# EFP01_-_Front_Panel_Board.net
KiCad netlist of a schematic drawn in EAGLE
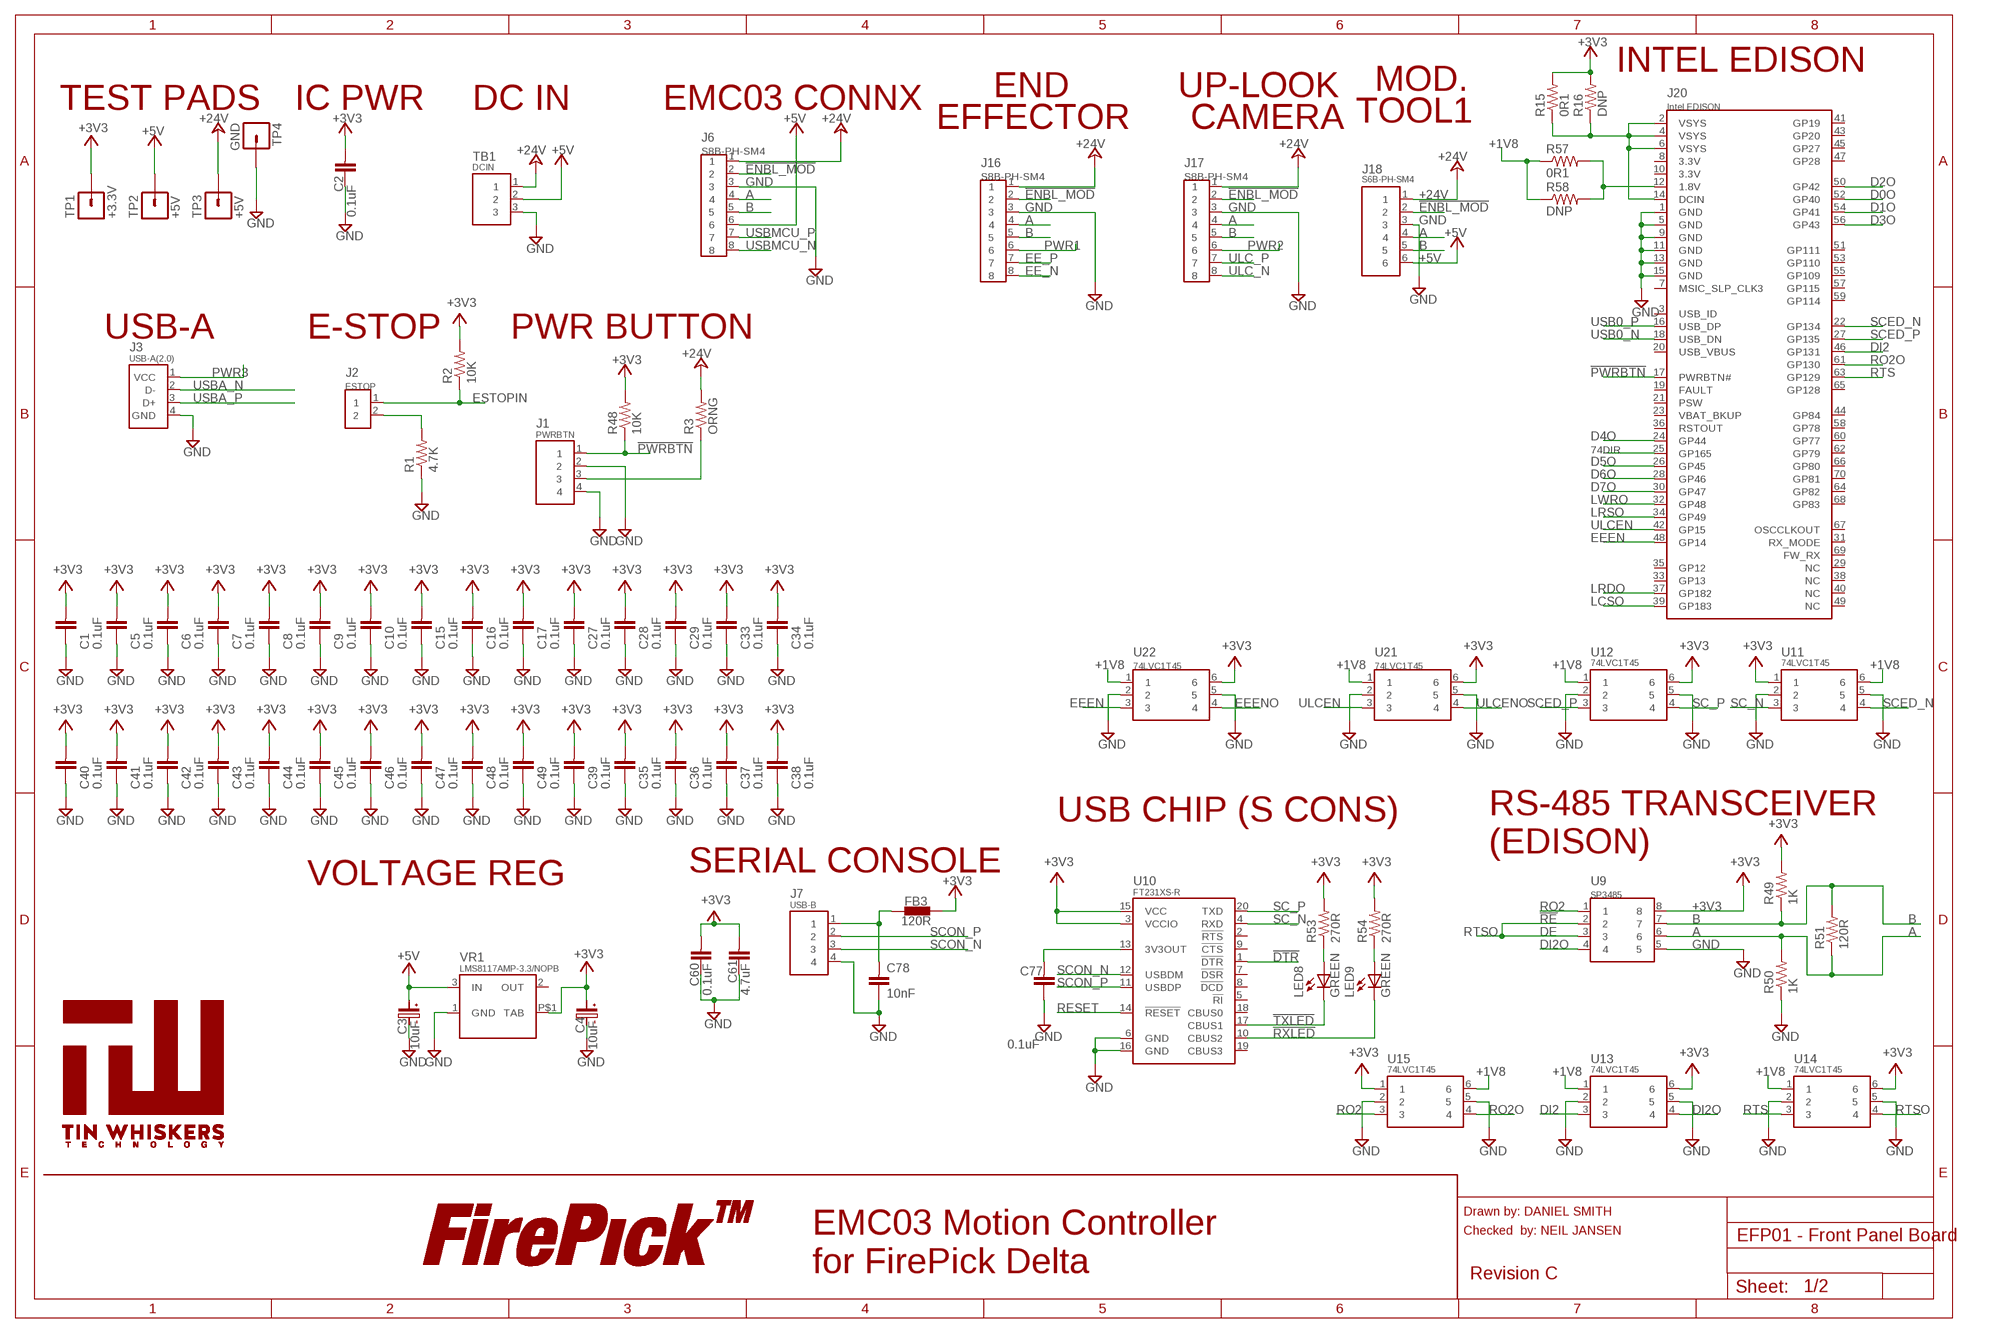
[diagram p0: schematic, sheet 1]
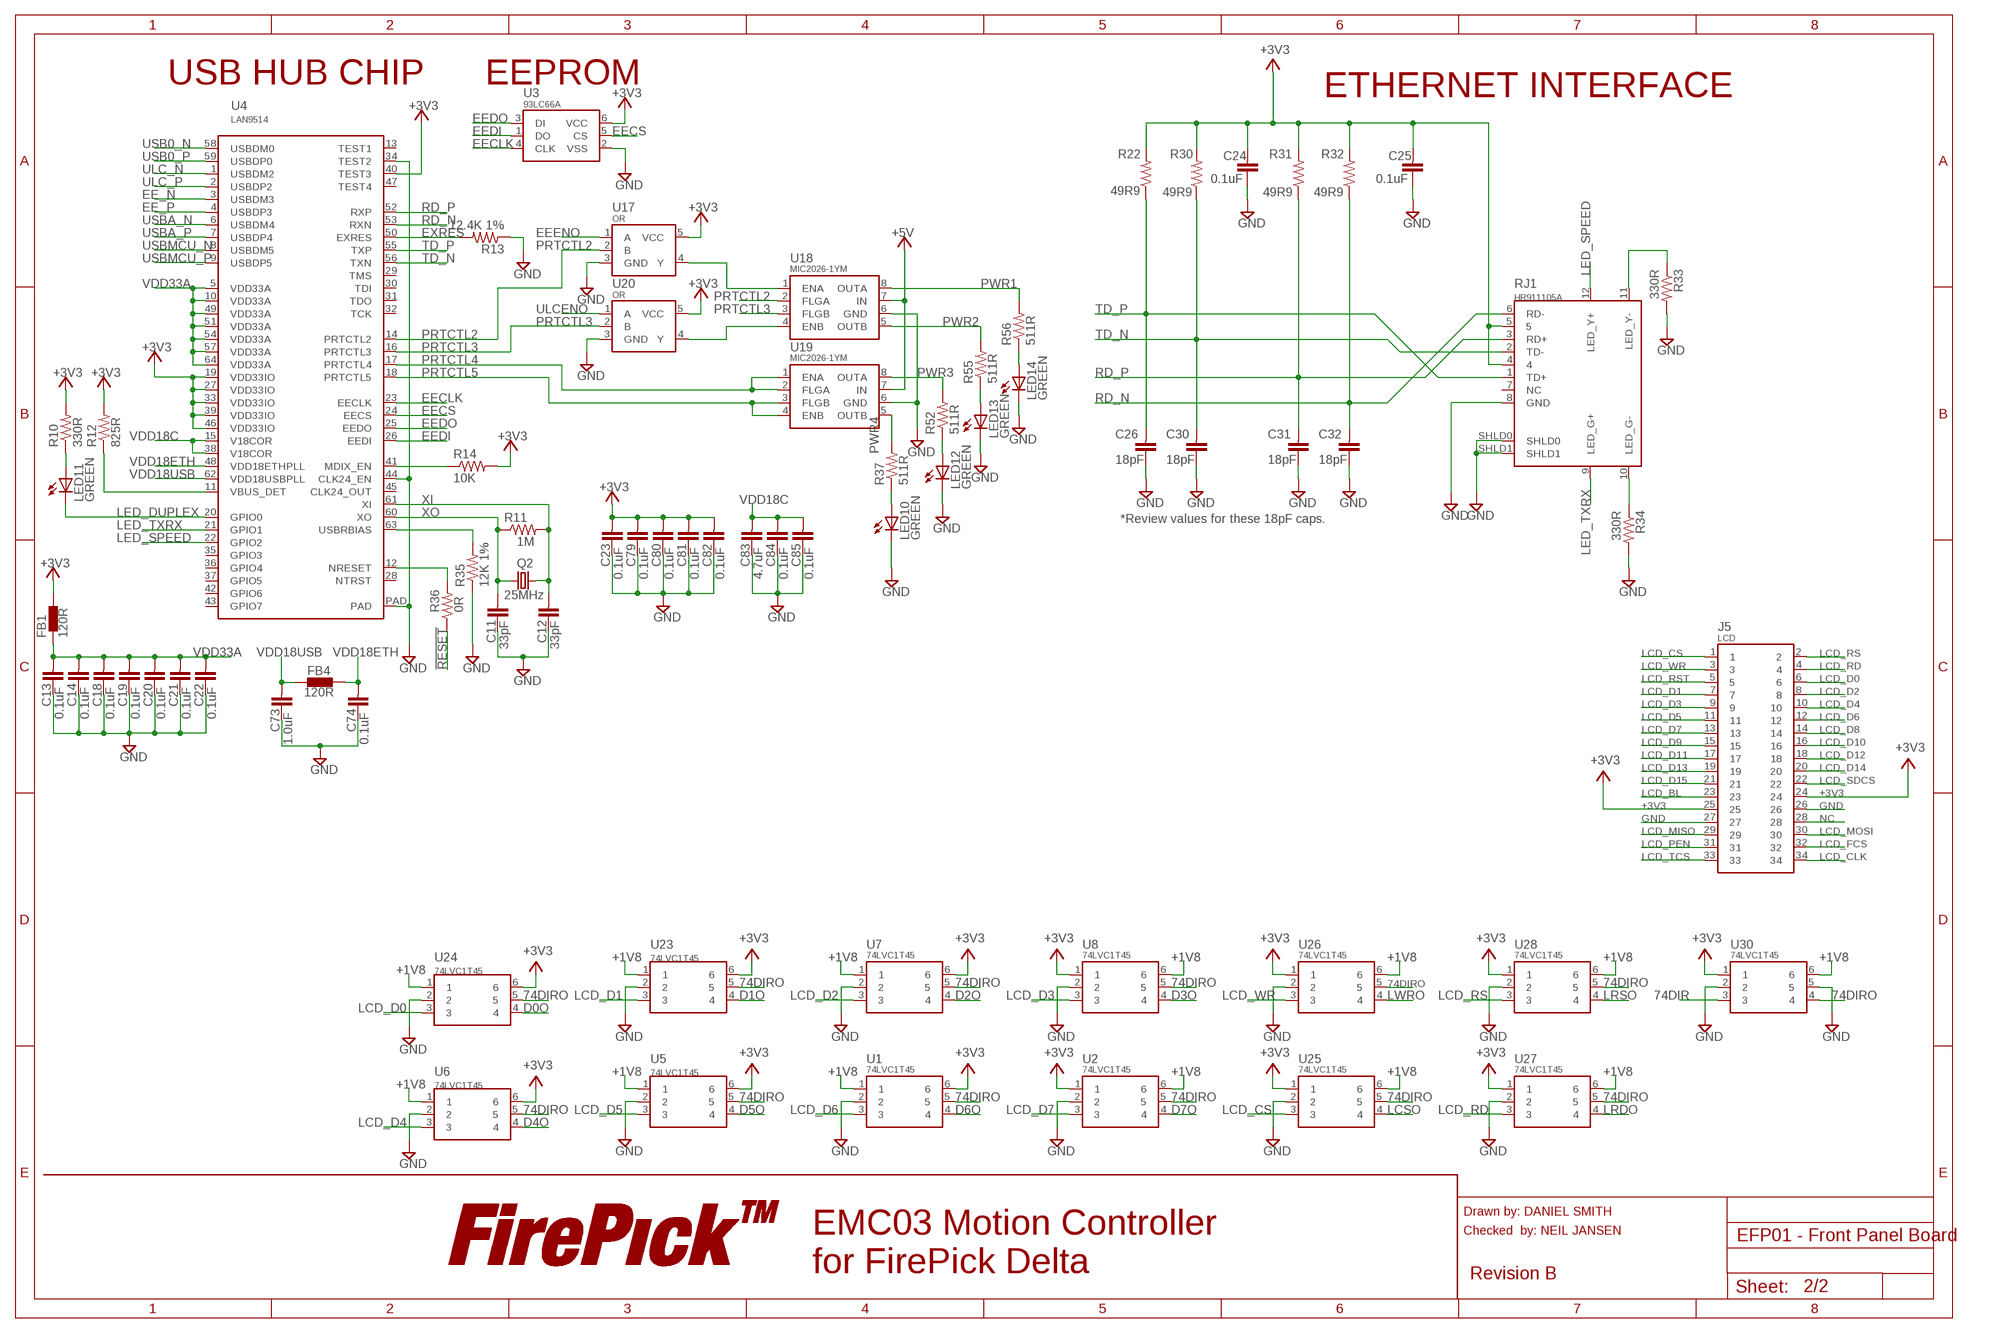
[diagram p1: schematic, sheet 2]

(export (version "E")
  (design (tool "Eeschema 10.0.6"))
  (components
    (comp (ref "C1")
      (value "0.1uF")
      (footprint "eagle-import:C0603")
      (fields (field (name "PARTNO") "GMK107BJ104KAHT"))
      (libsource (lib "eagle-import") (part "CPL-CAP-X5R-0603-0.1UF-35V"))
    )
    (comp (ref "C2")
      (value "0.1uF")
      (footprint "eagle-import:C0603")
      (fields (field (name "PARTNO") "GMK107BJ104KAHT"))
      (libsource (lib "eagle-import") (part "CPL-CAP-X5R-0603-0.1UF-35V"))
    )
    (comp (ref "C3")
      (value "10uF")
      (footprint "eagle-import:C-SMD-6.3MM")
      (fields (field (name "PARTNO") "EMVH350ADA100MF60G"))
      (libsource (lib "eagle-import") (part "CPL-CAP-ALU-6.4MM-10UF-10V"))
    )
    (comp (ref "C4")
      (value "10uF")
      (footprint "eagle-import:C-SMD-6.3MM")
      (fields (field (name "PARTNO") "EMVH350ADA100MF60G"))
      (libsource (lib "eagle-import") (part "CPL-CAP-ALU-6.4MM-10UF-10V"))
    )
    (comp (ref "C5")
      (value "0.1uF")
      (footprint "eagle-import:C0603")
      (fields (field (name "PARTNO") "GMK107BJ104KAHT"))
      (libsource (lib "eagle-import") (part "CPL-CAP-X5R-0603-0.1UF-35V"))
    )
    (comp (ref "C6")
      (value "0.1uF")
      (footprint "eagle-import:C0603")
      (fields (field (name "PARTNO") "GMK107BJ104KAHT"))
      (libsource (lib "eagle-import") (part "CPL-CAP-X5R-0603-0.1UF-35V"))
    )
    (comp (ref "C7")
      (value "0.1uF")
      (footprint "eagle-import:C0603")
      (fields (field (name "PARTNO") "GMK107BJ104KAHT"))
      (libsource (lib "eagle-import") (part "CPL-CAP-X5R-0603-0.1UF-35V"))
    )
    (comp (ref "C8")
      (value "0.1uF")
      (footprint "eagle-import:C0603")
      (fields (field (name "PARTNO") "GMK107BJ104KAHT"))
      (libsource (lib "eagle-import") (part "CPL-CAP-X5R-0603-0.1UF-35V"))
    )
    (comp (ref "C9")
      (value "0.1uF")
      (footprint "eagle-import:C0603")
      (fields (field (name "PARTNO") "GMK107BJ104KAHT"))
      (libsource (lib "eagle-import") (part "CPL-CAP-X5R-0603-0.1UF-35V"))
    )
    (comp (ref "C10")
      (value "0.1uF")
      (footprint "eagle-import:C0603")
      (fields (field (name "PARTNO") "GMK107BJ104KAHT"))
      (libsource (lib "eagle-import") (part "CPL-CAP-X5R-0603-0.1UF-35V"))
    )
    (comp (ref "C15")
      (value "0.1uF")
      (footprint "eagle-import:C0603")
      (fields (field (name "PARTNO") "GMK107BJ104KAHT"))
      (libsource (lib "eagle-import") (part "CPL-CAP-X5R-0603-0.1UF-35V"))
    )
    (comp (ref "C16")
      (value "0.1uF")
      (footprint "eagle-import:C0603")
      (fields (field (name "PARTNO") "GMK107BJ104KAHT"))
      (libsource (lib "eagle-import") (part "CPL-CAP-X5R-0603-0.1UF-35V"))
    )
    (comp (ref "C17")
      (value "0.1uF")
      (footprint "eagle-import:C0603")
      (fields (field (name "PARTNO") "GMK107BJ104KAHT"))
      (libsource (lib "eagle-import") (part "CPL-CAP-X5R-0603-0.1UF-35V"))
    )
    (comp (ref "C27")
      (value "0.1uF")
      (footprint "eagle-import:C0603")
      (fields (field (name "PARTNO") "GMK107BJ104KAHT"))
      (libsource (lib "eagle-import") (part "CPL-CAP-X5R-0603-0.1UF-35V"))
    )
    (comp (ref "C28")
      (value "0.1uF")
      (footprint "eagle-import:C0603")
      (fields (field (name "PARTNO") "GMK107BJ104KAHT"))
      (libsource (lib "eagle-import") (part "CPL-CAP-X5R-0603-0.1UF-35V"))
    )
    (comp (ref "C29")
      (value "0.1uF")
      (footprint "eagle-import:C0603")
      (fields (field (name "PARTNO") "GMK107BJ104KAHT"))
      (libsource (lib "eagle-import") (part "CPL-CAP-X5R-0603-0.1UF-35V"))
    )
    (comp (ref "C33")
      (value "0.1uF")
      (footprint "eagle-import:C0603")
      (fields (field (name "PARTNO") "GMK107BJ104KAHT"))
      (libsource (lib "eagle-import") (part "CPL-CAP-X5R-0603-0.1UF-35V"))
    )
    (comp (ref "C34")
      (value "0.1uF")
      (footprint "eagle-import:C0603")
      (fields (field (name "PARTNO") "GMK107BJ104KAHT"))
      (libsource (lib "eagle-import") (part "CPL-CAP-X5R-0603-0.1UF-35V"))
    )
    (comp (ref "C35")
      (value "0.1uF")
      (footprint "eagle-import:C0603")
      (fields (field (name "PARTNO") "GMK107BJ104KAHT"))
      (libsource (lib "eagle-import") (part "CPL-CAP-X5R-0603-0.1UF-35V"))
    )
    (comp (ref "C36")
      (value "0.1uF")
      (footprint "eagle-import:C0603")
      (fields (field (name "PARTNO") "GMK107BJ104KAHT"))
      (libsource (lib "eagle-import") (part "CPL-CAP-X5R-0603-0.1UF-35V"))
    )
    (comp (ref "C37")
      (value "0.1uF")
      (footprint "eagle-import:C0603")
      (fields (field (name "PARTNO") "GMK107BJ104KAHT"))
      (libsource (lib "eagle-import") (part "CPL-CAP-X5R-0603-0.1UF-35V"))
    )
    (comp (ref "C38")
      (value "0.1uF")
      (footprint "eagle-import:C0603")
      (fields (field (name "PARTNO") "GMK107BJ104KAHT"))
      (libsource (lib "eagle-import") (part "CPL-CAP-X5R-0603-0.1UF-35V"))
    )
    (comp (ref "C39")
      (value "0.1uF")
      (footprint "eagle-import:C0603")
      (fields (field (name "PARTNO") "GMK107BJ104KAHT"))
      (libsource (lib "eagle-import") (part "CPL-CAP-X5R-0603-0.1UF-35V"))
    )
    (comp (ref "C40")
      (value "0.1uF")
      (footprint "eagle-import:C0603")
      (fields (field (name "PARTNO") "GMK107BJ104KAHT"))
      (libsource (lib "eagle-import") (part "CPL-CAP-X5R-0603-0.1UF-35V"))
    )
    (comp (ref "C41")
      (value "0.1uF")
      (footprint "eagle-import:C0603")
      (fields (field (name "PARTNO") "GMK107BJ104KAHT"))
      (libsource (lib "eagle-import") (part "CPL-CAP-X5R-0603-0.1UF-35V"))
    )
    (comp (ref "C42")
      (value "0.1uF")
      (footprint "eagle-import:C0603")
      (fields (field (name "PARTNO") "GMK107BJ104KAHT"))
      (libsource (lib "eagle-import") (part "CPL-CAP-X5R-0603-0.1UF-35V"))
    )
    (comp (ref "C43")
      (value "0.1uF")
      (footprint "eagle-import:C0603")
      (fields (field (name "PARTNO") "GMK107BJ104KAHT"))
      (libsource (lib "eagle-import") (part "CPL-CAP-X5R-0603-0.1UF-35V"))
    )
    (comp (ref "C44")
      (value "0.1uF")
      (footprint "eagle-import:C0603")
      (fields (field (name "PARTNO") "GMK107BJ104KAHT"))
      (libsource (lib "eagle-import") (part "CPL-CAP-X5R-0603-0.1UF-35V"))
    )
    (comp (ref "C45")
      (value "0.1uF")
      (footprint "eagle-import:C0603")
      (fields (field (name "PARTNO") "GMK107BJ104KAHT"))
      (libsource (lib "eagle-import") (part "CPL-CAP-X5R-0603-0.1UF-35V"))
    )
    (comp (ref "C46")
      (value "0.1uF")
      (footprint "eagle-import:C0603")
      (fields (field (name "PARTNO") "GMK107BJ104KAHT"))
      (libsource (lib "eagle-import") (part "CPL-CAP-X5R-0603-0.1UF-35V"))
    )
    (comp (ref "C47")
      (value "0.1uF")
      (footprint "eagle-import:C0603")
      (fields (field (name "PARTNO") "GMK107BJ104KAHT"))
      (libsource (lib "eagle-import") (part "CPL-CAP-X5R-0603-0.1UF-35V"))
    )
    (comp (ref "C48")
      (value "0.1uF")
      (footprint "eagle-import:C0603")
      (fields (field (name "PARTNO") "GMK107BJ104KAHT"))
      (libsource (lib "eagle-import") (part "CPL-CAP-X5R-0603-0.1UF-35V"))
    )
    (comp (ref "C49")
      (value "0.1uF")
      (footprint "eagle-import:C0603")
      (fields (field (name "PARTNO") "GMK107BJ104KAHT"))
      (libsource (lib "eagle-import") (part "CPL-CAP-X5R-0603-0.1UF-35V"))
    )
    (comp (ref "C60")
      (value "0.1uF")
      (footprint "eagle-import:C0603")
      (fields (field (name "PARTNO") "GMK107BJ104KAHT"))
      (libsource (lib "eagle-import") (part "CPL-CAP-X5R-0603-0.1UF-35V"))
    )
    (comp (ref "C61")
      (value "4.7uF")
      (footprint "eagle-import:C0603")
      (fields (field (name "PARTNO") "GRM188C81E475KE11D"))
      (libsource (lib "eagle-import") (part "CPL-CAP-X5R-0603-4.7UF-10V"))
    )
    (comp (ref "C77")
      (value "0.1uF")
      (footprint "eagle-import:C0603")
      (fields (field (name "PARTNO") "GMK107BJ104KAHT"))
      (libsource (lib "eagle-import") (part "CPL-CAP-X7R-0603-0.1UF-35V"))
    )
    (comp (ref "C78")
      (value "10nF")
      (footprint "eagle-import:C0603")
      (fields (field (name "PARTNO") "GRM188R71H103KA01D"))
      (libsource (lib "eagle-import") (part "CPL-CAP-X7R-10NF-16V"))
    )
    (comp (ref "FB3")
      (value "120R")
      (footprint "eagle-import:F0603")
      (fields (field (name "PARTNO") "BLM18AG121SN1D"))
      (libsource (lib "eagle-import") (part "CPL-IND-FER-120OHM-2A"))
    )
    (comp (ref "J1")
      (value "PWRBTN")
      (footprint "eagle-import:CON-JST-PH-2.0MM-4P-SMT-VRT")
      (fields (field (name "PARTNO") "S4B-PH-SM4-TB(LF)(SN)"))
      (libsource (lib "eagle-import") (part "CPL-CON-JST-2.0MM-4P-M-SMT-VRT"))
    )
    (comp (ref "J2")
      (value "ESTOP")
      (footprint "eagle-import:CON-JST-PH-2.0MM-2P-SMT-VRT")
      (fields (field (name "PARTNO") "S2B-PH-SM4-TB(LF)(SN)"))
      (libsource (lib "eagle-import") (part "CPL-CON-JST-2.0MM-2P-M-SMT-VRT"))
    )
    (comp (ref "J3")
      (value "USB-A(2.0)")
      (footprint "eagle-import:USB-A-THRU-VERT-2.0")
      (fields (field (name "PARTNO") "1734085-1"))
      (libsource (lib "eagle-import") (part "CPL-CON-USB-A-THRU-VERT-2.0"))
    )
    (comp (ref "J6")
      (value "S8B-PH-SM4")
      (footprint "eagle-import:CON-JST-PH-2.0MM-8P-SMT-VRT")
      (fields (field (name "PARTNO") "B8B-PH-SM4-TB(LF)(SN)"))
      (libsource (lib "eagle-import") (part "CPL-CON-JST-2.0MM-8P-SMT-VRT"))
    )
    (comp (ref "J7")
      (value "USB-B")
      (footprint "eagle-import:USB-B(SMT)-VERT-1734517")
      (fields (field (name "PARTNO") "1734517-1"))
      (libsource (lib "eagle-import") (part "CPL-CON-USB-B-SMT-VERT"))
    )
    (comp (ref "J16")
      (value "S8B-PH-SM4")
      (footprint "eagle-import:CON-JST-PH-2.0MM-8P-SMT-VRT")
      (fields (field (name "PARTNO") "B8B-PH-SM4-TB(LF)(SN)"))
      (libsource (lib "eagle-import") (part "CPL-CON-JST-2.0MM-8P-SMT-VRT"))
    )
    (comp (ref "J17")
      (value "S8B-PH-SM4")
      (footprint "eagle-import:CON-JST-PH-2.0MM-8P-SMT-VRT")
      (fields (field (name "PARTNO") "B8B-PH-SM4-TB(LF)(SN)"))
      (libsource (lib "eagle-import") (part "CPL-CON-JST-2.0MM-8P-SMT-VRT"))
    )
    (comp (ref "J18")
      (value "S6B-PH-SM4")
      (footprint "eagle-import:CON-JST-PH-2.00MM-6P-SMT-VRT")
      (fields (field (name "PARTNO") "B6B-PH-SM4-TB(LF)(SN)"))
      (libsource (lib "eagle-import") (part "CPL-CON-JST-2.0MM-6P-SMT-VRT"))
    )
    (comp (ref "J20")
      (value "Intel EDISON")
      (footprint "eagle-import:DF40HC(3.0)-70DS-0.4V(51)")
      (fields (field (name "PARTNO") "DF40HC(3.0)-70DS-0.4V(51)"))
      (libsource (lib "eagle-import") (part "CPL-SBC-INTEL-EDISON"))
    )
    (comp (ref "LED8")
      (value "GREEN")
      (footprint "eagle-import:LED0603")
      (fields (field (name "PARTNO") "SML-D12M8WT86"))
      (libsource (lib "eagle-import") (part "CPL-LED-0603-GREEN"))
    )
    (comp (ref "LED9")
      (value "GREEN")
      (footprint "eagle-import:LED0603")
      (fields (field (name "PARTNO") "SML-D12M8WT86"))
      (libsource (lib "eagle-import") (part "CPL-LED-0603-GREEN"))
    )
    (comp (ref "LOGO1")
      (value "LOGO-FIREPICKLARGE")
      (footprint "eagle-import:LOGO-FIREPICK")
      (libsource (lib "eagle-import") (part "LOGO-FIREPICKLARGE"))
    )
    (comp (ref "R1")
      (value "4.7K")
      (footprint "eagle-import:R0603")
      (fields (field (name "PARTNO") "RC0603FR-074K7L"))
      (libsource (lib "eagle-import") (part "CPL-RES-0603-4.7K-0.1W"))
    )
    (comp (ref "R2")
      (value "10K")
      (footprint "eagle-import:R0603")
      (fields (field (name "PARTNO") "RC0603FR-0710KL"))
      (libsource (lib "eagle-import") (part "CPL-RES-0603-10K-0.1W"))
    )
    (comp (ref "R3")
      (value "ORNG")
      (footprint "eagle-import:R0603")
      (fields (field (name "PARTNO") "RC0603JR-070RL"))
      (libsource (lib "eagle-import") (part "CPL-RES-0603-0-0.1W"))
    )
    (comp (ref "R15")
      (value "0R1")
      (footprint "eagle-import:R0603")
      (fields (field (name "PARTNO") "RL0603FR-070R1L"))
      (libsource (lib "eagle-import") (part "CPL-RES-0603-0.1-0.1W"))
    )
    (comp (ref "R16")
      (value "DNP")
      (footprint "eagle-import:R0603")
      (fields (field (name "PARTNO") "RC0603JR-070RL"))
      (libsource (lib "eagle-import") (part "CPL-RES-0603-0-0.1W"))
    )
    (comp (ref "R48")
      (value "10K")
      (footprint "eagle-import:R0603")
      (fields (field (name "PARTNO") "RC0603FR-0710KL"))
      (libsource (lib "eagle-import") (part "CPL-RES-0603-10K-0.1W"))
    )
    (comp (ref "R49")
      (value "1K")
      (footprint "eagle-import:R0603")
      (fields (field (name "PARTNO") "RC0603FR-071KL"))
      (libsource (lib "eagle-import") (part "CPL-RES-0603-1K-0.1W"))
    )
    (comp (ref "R50")
      (value "1K")
      (footprint "eagle-import:R0603")
      (fields (field (name "PARTNO") "RC0603FR-071KL"))
      (libsource (lib "eagle-import") (part "CPL-RES-0603-1K-0.1W"))
    )
    (comp (ref "R51")
      (value "120R")
      (footprint "eagle-import:R0603")
      (fields (field (name "PARTNO") "RC0603FR-07120RL"))
      (libsource (lib "eagle-import") (part "CPL-RES-0603-120-0.1W"))
    )
    (comp (ref "R53")
      (value "270R")
      (footprint "eagle-import:R0603")
      (fields (field (name "PARTNO") "RC0603FR-07270RL"))
      (libsource (lib "eagle-import") (part "CPL-RES-0603-270-0.1W"))
    )
    (comp (ref "R54")
      (value "270R")
      (footprint "eagle-import:R0603")
      (fields (field (name "PARTNO") "RC0603FR-07270RL"))
      (libsource (lib "eagle-import") (part "CPL-RES-0603-270-0.1W"))
    )
    (comp (ref "R57")
      (value "0R1")
      (footprint "eagle-import:R0603")
      (fields (field (name "PARTNO") "RL0603FR-070R1L"))
      (libsource (lib "eagle-import") (part "CPL-RES-0603-0.1-0.1W"))
    )
    (comp (ref "R58")
      (value "DNP")
      (footprint "eagle-import:R0603")
      (fields (field (name "PARTNO") "RC0603JR-070RL"))
      (libsource (lib "eagle-import") (part "CPL-RES-0603-0-0.1W"))
    )
    (comp (ref "TB1")
      (value "DCIN")
      (footprint "eagle-import:TBLOCK-3-5MM-OSTTH030160")
      (fields (field (name "PARTNO") "OSTTH030160"))
      (libsource (lib "eagle-import") (part "CPL-TBLK-SCR-3CKT-5.0MM-OST"))
    )
    (comp (ref "TP1")
      (value "+3.3V")
      (footprint "eagle-import:TESTPAD")
      (libsource (lib "eagle-import") (part "TPAD"))
    )
    (comp (ref "TP2")
      (value "+5V")
      (footprint "eagle-import:TESTPAD")
      (libsource (lib "eagle-import") (part "TPAD"))
    )
    (comp (ref "TP3")
      (value "+5V")
      (footprint "eagle-import:TESTPAD")
      (libsource (lib "eagle-import") (part "TPAD"))
    )
    (comp (ref "TP4")
      (value "GND")
      (footprint "eagle-import:TESTPAD")
      (libsource (lib "eagle-import") (part "TPAD"))
    )
    (comp (ref "U$1")
      (value "TIN-WHISKERSTSTOP")
      (footprint "eagle-import:TIN-WHISKERS-TSTOP")
      (libsource (lib "eagle-import") (part "TIN-WHISKERSTSTOP"))
    )
    (comp (ref "U9")
      (value "SP3485")
      (footprint "eagle-import:SOICN-8")
      (libsource (lib "eagle-import") (part "SP3485"))
    )
    (comp (ref "U10")
      (value "FT231XS-R")
      (footprint "eagle-import:20-SSOP")
      (libsource (lib "eagle-import") (part "CPL-USB-FT2321XS"))
    )
    (comp (ref "U11")
      (value "74LVC1T45")
      (footprint "eagle-import:SOT-363")
      (fields (field (name "PARTNO") "74LVC1T45GW,125"))
      (libsource (lib "eagle-import") (part "CPL-TRS-74LVC1T45"))
    )
    (comp (ref "U12")
      (value "74LVC1T45")
      (footprint "eagle-import:SOT-363")
      (fields (field (name "PARTNO") "74LVC1T45GW,125"))
      (libsource (lib "eagle-import") (part "CPL-TRS-74LVC1T45"))
    )
    (comp (ref "U13")
      (value "74LVC1T45")
      (footprint "eagle-import:SOT-363")
      (fields (field (name "PARTNO") "74LVC1T45GW,125"))
      (libsource (lib "eagle-import") (part "CPL-TRS-74LVC1T45"))
    )
    (comp (ref "U14")
      (value "74LVC1T45")
      (footprint "eagle-import:SOT-363")
      (fields (field (name "PARTNO") "74LVC1T45GW,125"))
      (libsource (lib "eagle-import") (part "CPL-TRS-74LVC1T45"))
    )
    (comp (ref "U15")
      (value "74LVC1T45")
      (footprint "eagle-import:SOT-363")
      (fields (field (name "PARTNO") "74LVC1T45GW,125"))
      (libsource (lib "eagle-import") (part "CPL-TRS-74LVC1T45"))
    )
    (comp (ref "U21")
      (value "74LVC1T45")
      (footprint "eagle-import:SOT-363")
      (fields (field (name "PARTNO") "74LVC1T45GW,125"))
      (libsource (lib "eagle-import") (part "CPL-TRS-74LVC1T45"))
    )
    (comp (ref "U22")
      (value "74LVC1T45")
      (footprint "eagle-import:SOT-363")
      (fields (field (name "PARTNO") "74LVC1T45GW,125"))
      (libsource (lib "eagle-import") (part "CPL-TRS-74LVC1T45"))
    )
    (comp (ref "VR1")
      (value "LMS8117AMP-3.3/NOPB")
      (footprint "eagle-import:SOT-223")
      (libsource (lib "eagle-import") (part "CPL-REG-LIN-3.3V-1A"))
    )
    (comp (ref "C11")
      (value "33pF")
      (footprint "eagle-import:C0603")
      (fields (field (name "PARTNO") "C0603C330K5GACTU"))
      (libsource (lib "eagle-import") (part "CPL-CAP-C0G-0603-33PF-50V"))
    )
    (comp (ref "C12")
      (value "33pF")
      (footprint "eagle-import:C0603")
      (fields (field (name "PARTNO") "C0603C330K5GACTU"))
      (libsource (lib "eagle-import") (part "CPL-CAP-C0G-0603-33PF-50V"))
    )
    (comp (ref "C13")
      (value "0.1uF")
      (footprint "eagle-import:C0603")
      (fields (field (name "PARTNO") "GMK107BJ104KAHT"))
      (libsource (lib "eagle-import") (part "CPL-CAP-X5R-0603-0.1UF-35V"))
    )
    (comp (ref "C14")
      (value "0.1uF")
      (footprint "eagle-import:C0603")
      (fields (field (name "PARTNO") "GMK107BJ104KAHT"))
      (libsource (lib "eagle-import") (part "CPL-CAP-X5R-0603-0.1UF-35V"))
    )
    (comp (ref "C18")
      (value "0.1uF")
      (footprint "eagle-import:C0603")
      (fields (field (name "PARTNO") "GMK107BJ104KAHT"))
      (libsource (lib "eagle-import") (part "CPL-CAP-X5R-0603-0.1UF-35V"))
    )
    (comp (ref "C19")
      (value "0.1uF")
      (footprint "eagle-import:C0603")
      (fields (field (name "PARTNO") "GMK107BJ104KAHT"))
      (libsource (lib "eagle-import") (part "CPL-CAP-X5R-0603-0.1UF-35V"))
    )
    (comp (ref "C20")
      (value "0.1uF")
      (footprint "eagle-import:C0603")
      (fields (field (name "PARTNO") "GMK107BJ104KAHT"))
      (libsource (lib "eagle-import") (part "CPL-CAP-X5R-0603-0.1UF-35V"))
    )
    (comp (ref "C21")
      (value "0.1uF")
      (footprint "eagle-import:C0603")
      (fields (field (name "PARTNO") "GMK107BJ104KAHT"))
      (libsource (lib "eagle-import") (part "CPL-CAP-X5R-0603-0.1UF-35V"))
    )
    (comp (ref "C22")
      (value "0.1uF")
      (footprint "eagle-import:C0603")
      (fields (field (name "PARTNO") "GMK107BJ104KAHT"))
      (libsource (lib "eagle-import") (part "CPL-CAP-X5R-0603-0.1UF-35V"))
    )
    (comp (ref "C23")
      (value "0.1uF")
      (footprint "eagle-import:C0603")
      (fields (field (name "PARTNO") "GMK107BJ104KAHT"))
      (libsource (lib "eagle-import") (part "CPL-CAP-X5R-0603-0.1UF-35V"))
    )
    (comp (ref "C24")
      (value "0.1uF")
      (footprint "eagle-import:C0603")
      (fields (field (name "PARTNO") "GMK107BJ104KAHT"))
      (libsource (lib "eagle-import") (part "CPL-CAP-X7R-0603-0.1UF-35V"))
    )
    (comp (ref "C25")
      (value "0.1uF")
      (footprint "eagle-import:C0603")
      (fields (field (name "PARTNO") "GMK107BJ104KAHT"))
      (libsource (lib "eagle-import") (part "CPL-CAP-X7R-0603-0.1UF-35V"))
    )
    (comp (ref "C26")
      (value "18pF")
      (footprint "eagle-import:C0603")
      (fields (field (name "PARTNO") "GCM1885C1H180JA16D"))
      (libsource (lib "eagle-import") (part "CPL-CAP-C0G-0603-18PF-50V"))
    )
    (comp (ref "C30")
      (value "18pF")
      (footprint "eagle-import:C0603")
      (fields (field (name "PARTNO") "GCM1885C1H180JA16D"))
      (libsource (lib "eagle-import") (part "CPL-CAP-C0G-0603-18PF-50V"))
    )
    (comp (ref "C31")
      (value "18pF")
      (footprint "eagle-import:C0603")
      (fields (field (name "PARTNO") "GCM1885C1H180JA16D"))
      (libsource (lib "eagle-import") (part "CPL-CAP-C0G-0603-18PF-50V"))
    )
    (comp (ref "C32")
      (value "18pF")
      (footprint "eagle-import:C0603")
      (fields (field (name "PARTNO") "GCM1885C1H180JA16D"))
      (libsource (lib "eagle-import") (part "CPL-CAP-C0G-0603-18PF-50V"))
    )
    (comp (ref "C73")
      (value "1.0uF")
      (footprint "eagle-import:C0603")
      (fields (field (name "PARTNO") "UMK107AB7105KA-T"))
      (libsource (lib "eagle-import") (part "CPL-CAP-X5R-0603-1UF-50V"))
    )
    (comp (ref "C74")
      (value "0.1uF")
      (footprint "eagle-import:C0603")
      (fields (field (name "PARTNO") "GMK107BJ104KAHT"))
      (libsource (lib "eagle-import") (part "CPL-CAP-X5R-0603-0.1UF-35V"))
    )
    (comp (ref "C79")
      (value "0.1uF")
      (footprint "eagle-import:C0603")
      (fields (field (name "PARTNO") "GMK107BJ104KAHT"))
      (libsource (lib "eagle-import") (part "CPL-CAP-X5R-0603-0.1UF-35V"))
    )
    (comp (ref "C80")
      (value "0.1uF")
      (footprint "eagle-import:C0603")
      (fields (field (name "PARTNO") "GMK107BJ104KAHT"))
      (libsource (lib "eagle-import") (part "CPL-CAP-X5R-0603-0.1UF-35V"))
    )
    (comp (ref "C81")
      (value "0.1uF")
      (footprint "eagle-import:C0603")
      (fields (field (name "PARTNO") "GMK107BJ104KAHT"))
      (libsource (lib "eagle-import") (part "CPL-CAP-X5R-0603-0.1UF-35V"))
    )
    (comp (ref "C82")
      (value "0.1uF")
      (footprint "eagle-import:C0603")
      (fields (field (name "PARTNO") "GMK107BJ104KAHT"))
      (libsource (lib "eagle-import") (part "CPL-CAP-X5R-0603-0.1UF-35V"))
    )
    (comp (ref "C83")
      (value "4.7uF")
      (footprint "eagle-import:C0603")
      (fields (field (name "PARTNO") "GRM188C81E475KE11D"))
      (libsource (lib "eagle-import") (part "CPL-CAP-X5R-0603-4.7UF-10V"))
    )
    (comp (ref "C84")
      (value "0.1uF")
      (footprint "eagle-import:C0603")
      (fields (field (name "PARTNO") "GMK107BJ104KAHT"))
      (libsource (lib "eagle-import") (part "CPL-CAP-X5R-0603-0.1UF-35V"))
    )
    (comp (ref "C85")
      (value "0.1uF")
      (footprint "eagle-import:C0603")
      (fields (field (name "PARTNO") "GMK107BJ104KAHT"))
      (libsource (lib "eagle-import") (part "CPL-CAP-X5R-0603-0.1UF-35V"))
    )
    (comp (ref "FB1")
      (value "120R")
      (footprint "eagle-import:F0603")
      (fields (field (name "PARTNO") "BLM18AG121SN1D"))
      (libsource (lib "eagle-import") (part "CPL-IND-FER-120OHM-2A"))
    )
    (comp (ref "FB4")
      (value "120R")
      (footprint "eagle-import:F0603")
      (fields (field (name "PARTNO") "BLM18AG121SN1D"))
      (libsource (lib "eagle-import") (part "CPL-IND-FER-120OHM-2A"))
    )
    (comp (ref "J5")
      (value "LCD")
      (footprint "eagle-import:LCD-34P-3.2IN")
      (fields (field (name "PARTNO") "TSW-117-07-T-D"))
      (libsource (lib "eagle-import") (part "CPL-CON-LCD-HDR-0.1IN-17P2-F"))
    )
    (comp (ref "LED10")
      (value "GREEN")
      (footprint "eagle-import:LED0603")
      (fields (field (name "PARTNO") "SML-D12M8WT86"))
      (libsource (lib "eagle-import") (part "CPL-LED-0603-GREEN"))
    )
    (comp (ref "LED11")
      (value "GREEN")
      (footprint "eagle-import:LED0603")
      (fields (field (name "PARTNO") "SML-D12M8WT86"))
      (libsource (lib "eagle-import") (part "CPL-LED-0603-GREEN"))
    )
    (comp (ref "LED12")
      (value "GREEN")
      (footprint "eagle-import:LED0603")
      (fields (field (name "PARTNO") "SML-D12M8WT86"))
      (libsource (lib "eagle-import") (part "CPL-LED-0603-GREEN"))
    )
    (comp (ref "LED13")
      (value "GREEN")
      (footprint "eagle-import:LED0603")
      (fields (field (name "PARTNO") "SML-D12M8WT86"))
      (libsource (lib "eagle-import") (part "CPL-LED-0603-GREEN"))
    )
    (comp (ref "LED14")
      (value "GREEN")
      (footprint "eagle-import:LED0603")
      (fields (field (name "PARTNO") "SML-D12M8WT86"))
      (libsource (lib "eagle-import") (part "CPL-LED-0603-GREEN"))
    )
    (comp (ref "LOGO2")
      (value "LOGO-FIREPICKLARGE")
      (footprint "eagle-import:LOGO-FIREPICK")
      (libsource (lib "eagle-import") (part "LOGO-FIREPICKLARGE"))
    )
    (comp (ref "Q2")
      (value "25MHz")
      (footprint "eagle-import:HC-49_U-S")
      (fields (field (name "PARTNO") "HCM4925000000MABJ"))
      (libsource (lib "eagle-import") (part "CPL-OSC-CRY-25MHZ-18PF"))
    )
    (comp (ref "R10")
      (value "330R")
      (footprint "eagle-import:R0603")
      (fields (field (name "PARTNO") "RC0603FR-07330RL"))
      (libsource (lib "eagle-import") (part "CPL-RES-0603-330-0.1W"))
    )
    (comp (ref "R11")
      (value "1M")
      (footprint "eagle-import:R0603")
      (fields (field (name "PARTNO") "RC0603FR-071ML"))
      (libsource (lib "eagle-import") (part "CPL-RES-0603-1M-0.1W"))
    )
    (comp (ref "R12")
      (value "825R")
      (footprint "eagle-import:R0603")
      (fields (field (name "PARTNO") "RC0603FR-07825RL"))
      (libsource (lib "eagle-import") (part "CPL-RES-0603-825-0.1W"))
    )
    (comp (ref "R13")
      (value "12.4K 1%")
      (footprint "eagle-import:R0603")
      (fields (field (name "PARTNO") "RC0603FR-0712K4L"))
      (libsource (lib "eagle-import") (part "CPL-RES-0603-12.4K-0.1W"))
    )
    (comp (ref "R14")
      (value "10K")
      (footprint "eagle-import:R0603")
      (fields (field (name "PARTNO") "RC0603FR-0710KL"))
      (libsource (lib "eagle-import") (part "CPL-RES-0603-10K-0.1W"))
    )
    (comp (ref "R22")
      (value "49R9")
      (footprint "eagle-import:R0603")
      (fields (field (name "PARTNO") "RC0603FR-0749R9L"))
      (libsource (lib "eagle-import") (part "CPL-RES-0603-49.9-0.1W"))
    )
    (comp (ref "R30")
      (value "49R9")
      (footprint "eagle-import:R0603")
      (fields (field (name "PARTNO") "RC0603FR-0749R9L"))
      (libsource (lib "eagle-import") (part "CPL-RES-0603-49.9-0.1W"))
    )
    (comp (ref "R31")
      (value "49R9")
      (footprint "eagle-import:R0603")
      (fields (field (name "PARTNO") "RC0603FR-0749R9L"))
      (libsource (lib "eagle-import") (part "CPL-RES-0603-49.9-0.1W"))
    )
    (comp (ref "R32")
      (value "49R9")
      (footprint "eagle-import:R0603")
      (fields (field (name "PARTNO") "RC0603FR-0749R9L"))
      (libsource (lib "eagle-import") (part "CPL-RES-0603-49.9-0.1W"))
    )
    (comp (ref "R33")
      (value "330R")
      (footprint "eagle-import:R0603")
      (fields (field (name "PARTNO") "RC0603FR-07330RL"))
      (libsource (lib "eagle-import") (part "CPL-RES-0603-330-0.1W"))
    )
    (comp (ref "R34")
      (value "330R")
      (footprint "eagle-import:R0603")
      (fields (field (name "PARTNO") "RC0603FR-07330RL"))
      (libsource (lib "eagle-import") (part "CPL-RES-0603-330-0.1W"))
    )
    (comp (ref "R35")
      (value "12K 1%")
      (footprint "eagle-import:R0603")
      (fields (field (name "PARTNO") "RC0603FR-0712KL"))
      (libsource (lib "eagle-import") (part "CPL-RES-0603-12K-0.1W"))
    )
    (comp (ref "R36")
      (value "0R")
      (footprint "eagle-import:R0603")
      (fields (field (name "PARTNO") "RC0603JR-070RL"))
      (libsource (lib "eagle-import") (part "CPL-RES-0603-0-0.1W"))
    )
    (comp (ref "R37")
      (value "511R")
      (footprint "eagle-import:R0603")
      (fields (field (name "PARTNO") "RC0603FR-07511RL"))
      (libsource (lib "eagle-import") (part "CPL-RES-0603-511-0.1W"))
    )
    (comp (ref "R52")
      (value "511R")
      (footprint "eagle-import:R0603")
      (fields (field (name "PARTNO") "RC0603FR-07511RL"))
      (libsource (lib "eagle-import") (part "CPL-RES-0603-511-0.1W"))
    )
    (comp (ref "R55")
      (value "511R")
      (footprint "eagle-import:R0603")
      (fields (field (name "PARTNO") "RC0603FR-07511RL"))
      (libsource (lib "eagle-import") (part "CPL-RES-0603-511-0.1W"))
    )
    (comp (ref "R56")
      (value "511R")
      (footprint "eagle-import:R0603")
      (fields (field (name "PARTNO") "RC0603FR-07511RL"))
      (libsource (lib "eagle-import") (part "CPL-RES-0603-511-0.1W"))
    )
    (comp (ref "RJ1")
      (value "HR911105A")
      (footprint "eagle-import:MAGJACK(HR911105A)")
      (libsource (lib "eagle-import") (part "CPL-ETH-MACJACK-LED-SHLD"))
    )
    (comp (ref "U1")
      (value "74LVC1T45")
      (footprint "eagle-import:SOT-363")
      (fields (field (name "PARTNO") "74LVC1T45GW,125"))
      (libsource (lib "eagle-import") (part "CPL-TRS-74LVC1T45"))
    )
    (comp (ref "U2")
      (value "74LVC1T45")
      (footprint "eagle-import:SOT-363")
      (fields (field (name "PARTNO") "74LVC1T45GW,125"))
      (libsource (lib "eagle-import") (part "CPL-TRS-74LVC1T45"))
    )
    (comp (ref "U3")
      (value "93LC66A")
      (footprint "eagle-import:SOT-23-6")
      (fields (field (name "PARTNO") "93LC66A-I/SN"))
      (libsource (lib "eagle-import") (part "CPL-MEM-512KB-EEPROM-SOT23-6"))
    )
    (comp (ref "U4")
      (value "LAN9514")
      (footprint "eagle-import:64-QFN")
      (fields (field (name "PARTNO") "LAN9514-JZX"))
      (libsource (lib "eagle-import") (part "CPL-USB-HUB-LAN9514"))
    )
    (comp (ref "U5")
      (value "74LVC1T45")
      (footprint "eagle-import:SOT-363")
      (fields (field (name "PARTNO") "74LVC1T45GW,125"))
      (libsource (lib "eagle-import") (part "CPL-TRS-74LVC1T45"))
    )
    (comp (ref "U6")
      (value "74LVC1T45")
      (footprint "eagle-import:SOT-363")
      (fields (field (name "PARTNO") "74LVC1T45GW,125"))
      (libsource (lib "eagle-import") (part "CPL-TRS-74LVC1T45"))
    )
    (comp (ref "U7")
      (value "74LVC1T45")
      (footprint "eagle-import:SOT-363")
      (fields (field (name "PARTNO") "74LVC1T45GW,125"))
      (libsource (lib "eagle-import") (part "CPL-TRS-74LVC1T45"))
    )
    (comp (ref "U8")
      (value "74LVC1T45")
      (footprint "eagle-import:SOT-363")
      (fields (field (name "PARTNO") "74LVC1T45GW,125"))
      (libsource (lib "eagle-import") (part "CPL-TRS-74LVC1T45"))
    )
    (comp (ref "U17")
      (value "OR")
      (footprint "eagle-import:SOT-23-5")
      (fields (field (name "PARTNO") "SN74LVC1G32DBVR"))
      (libsource (lib "eagle-import") (part "CPL-IC-LOGIC-OR-1CH-74LVC"))
    )
    (comp (ref "U18")
      (value "MIC2026-1YM")
      (footprint "eagle-import:SOIC-8")
      (libsource (lib "eagle-import") (part "CPL-PWR-SWI-2CH-MIC2026-1XX"))
    )
    (comp (ref "U19")
      (value "MIC2026-1YM")
      (footprint "eagle-import:SOIC-8")
      (libsource (lib "eagle-import") (part "CPL-PWR-SWI-2CH-MIC2026-1XX"))
    )
    (comp (ref "U20")
      (value "OR")
      (footprint "eagle-import:SOT-23-5")
      (fields (field (name "PARTNO") "SN74LVC1G32DBVR"))
      (libsource (lib "eagle-import") (part "CPL-IC-LOGIC-OR-1CH-74LVC"))
    )
    (comp (ref "U23")
      (value "74LVC1T45")
      (footprint "eagle-import:SOT-363")
      (fields (field (name "PARTNO") "74LVC1T45GW,125"))
      (libsource (lib "eagle-import") (part "CPL-TRS-74LVC1T45"))
    )
    (comp (ref "U24")
      (value "74LVC1T45")
      (footprint "eagle-import:SOT-363")
      (fields (field (name "PARTNO") "74LVC1T45GW,125"))
      (libsource (lib "eagle-import") (part "CPL-TRS-74LVC1T45"))
    )
    (comp (ref "U25")
      (value "74LVC1T45")
      (footprint "eagle-import:SOT-363")
      (fields (field (name "PARTNO") "74LVC1T45GW,125"))
      (libsource (lib "eagle-import") (part "CPL-TRS-74LVC1T45"))
    )
    (comp (ref "U26")
      (value "74LVC1T45")
      (footprint "eagle-import:SOT-363")
      (fields (field (name "PARTNO") "74LVC1T45GW,125"))
      (libsource (lib "eagle-import") (part "CPL-TRS-74LVC1T45"))
    )
    (comp (ref "U27")
      (value "74LVC1T45")
      (footprint "eagle-import:SOT-363")
      (fields (field (name "PARTNO") "74LVC1T45GW,125"))
      (libsource (lib "eagle-import") (part "CPL-TRS-74LVC1T45"))
    )
    (comp (ref "U28")
      (value "74LVC1T45")
      (footprint "eagle-import:SOT-363")
      (fields (field (name "PARTNO") "74LVC1T45GW,125"))
      (libsource (lib "eagle-import") (part "CPL-TRS-74LVC1T45"))
    )
    (comp (ref "U30")
      (value "74LVC1T45")
      (footprint "eagle-import:SOT-363")
      (fields (field (name "PARTNO") "74LVC1T45GW,125"))
      (libsource (lib "eagle-import") (part "CPL-TRS-74LVC1T45"))
    )
  )
  (nets
    (net (code "1") (name "+1V8") (class "Default")
      (node (ref "R57") (pin "1") (pinfunction "1_1") (pintype "passive"))
      (node (ref "R58") (pin "1") (pinfunction "1_1") (pintype "passive"))
      (node (ref "U1") (pin "1") (pinfunction "1_1") (pintype "bidirectional"))
      (node (ref "U11") (pin "6") (pinfunction "6_6") (pintype "bidirectional"))
      (node (ref "U12") (pin "1") (pinfunction "1_1") (pintype "bidirectional"))
      (node (ref "U13") (pin "1") (pinfunction "1_1") (pintype "bidirectional"))
      (node (ref "U14") (pin "1") (pinfunction "1_1") (pintype "bidirectional"))
      (node (ref "U15") (pin "6") (pinfunction "6_6") (pintype "bidirectional"))
      (node (ref "U2") (pin "6") (pinfunction "6_6") (pintype "bidirectional"))
      (node (ref "U21") (pin "1") (pinfunction "1_1") (pintype "bidirectional"))
      (node (ref "U22") (pin "1") (pinfunction "1_1") (pintype "bidirectional"))
      (node (ref "U23") (pin "1") (pinfunction "1_1") (pintype "bidirectional"))
      (node (ref "U24") (pin "1") (pinfunction "1_1") (pintype "bidirectional"))
      (node (ref "U25") (pin "6") (pinfunction "6_6") (pintype "bidirectional"))
      (node (ref "U26") (pin "6") (pinfunction "6_6") (pintype "bidirectional"))
      (node (ref "U27") (pin "6") (pinfunction "6_6") (pintype "bidirectional"))
      (node (ref "U28") (pin "6") (pinfunction "6_6") (pintype "bidirectional"))
      (node (ref "U30") (pin "6") (pinfunction "6_6") (pintype "bidirectional"))
      (node (ref "U5") (pin "1") (pinfunction "1_1") (pintype "bidirectional"))
      (node (ref "U6") (pin "1") (pinfunction "1_1") (pintype "bidirectional"))
      (node (ref "U7") (pin "1") (pinfunction "1_1") (pintype "bidirectional"))
      (node (ref "U8") (pin "6") (pinfunction "6_6") (pintype "bidirectional"))
    )
    (net (code "2") (name "+3V3") (class "Default")
      (node (ref "C1") (pin "2") (pinfunction "2_2") (pintype "passive"))
      (node (ref "C10") (pin "2") (pinfunction "2_2") (pintype "passive"))
      (node (ref "C15") (pin "2") (pinfunction "2_2") (pintype "passive"))
      (node (ref "C16") (pin "2") (pinfunction "2_2") (pintype "passive"))
      (node (ref "C17") (pin "2") (pinfunction "2_2") (pintype "passive"))
      (node (ref "C2") (pin "2") (pinfunction "2_2") (pintype "passive"))
      (node (ref "C23") (pin "2") (pinfunction "2_2") (pintype "passive"))
      (node (ref "C24") (pin "2") (pinfunction "2_2") (pintype "passive"))
      (node (ref "C25") (pin "2") (pinfunction "2_2") (pintype "passive"))
      (node (ref "C27") (pin "2") (pinfunction "2_2") (pintype "passive"))
      (node (ref "C28") (pin "2") (pinfunction "2_2") (pintype "passive"))
      (node (ref "C29") (pin "2") (pinfunction "2_2") (pintype "passive"))
      (node (ref "C33") (pin "2") (pinfunction "2_2") (pintype "passive"))
      (node (ref "C34") (pin "2") (pinfunction "2_2") (pintype "passive"))
      (node (ref "C35") (pin "2") (pinfunction "2_2") (pintype "passive"))
      (node (ref "C36") (pin "2") (pinfunction "2_2") (pintype "passive"))
      (node (ref "C37") (pin "2") (pinfunction "2_2") (pintype "passive"))
      (node (ref "C38") (pin "2") (pinfunction "2_2") (pintype "passive"))
      (node (ref "C39") (pin "2") (pinfunction "2_2") (pintype "passive"))
      (node (ref "C4") (pin "POS") (pinfunction "POS_POS") (pintype "passive"))
      (node (ref "C40") (pin "2") (pinfunction "2_2") (pintype "passive"))
      (node (ref "C41") (pin "2") (pinfunction "2_2") (pintype "passive"))
      (node (ref "C42") (pin "2") (pinfunction "2_2") (pintype "passive"))
      (node (ref "C43") (pin "2") (pinfunction "2_2") (pintype "passive"))
      (node (ref "C44") (pin "2") (pinfunction "2_2") (pintype "passive"))
      (node (ref "C45") (pin "2") (pinfunction "2_2") (pintype "passive"))
      (node (ref "C46") (pin "2") (pinfunction "2_2") (pintype "passive"))
      (node (ref "C47") (pin "2") (pinfunction "2_2") (pintype "passive"))
      (node (ref "C48") (pin "2") (pinfunction "2_2") (pintype "passive"))
      (node (ref "C49") (pin "2") (pinfunction "2_2") (pintype "passive"))
      (node (ref "C5") (pin "2") (pinfunction "2_2") (pintype "passive"))
      (node (ref "C6") (pin "2") (pinfunction "2_2") (pintype "passive"))
      (node (ref "C60") (pin "2") (pinfunction "2_2") (pintype "passive"))
      (node (ref "C61") (pin "2") (pinfunction "2_2") (pintype "passive"))
      (node (ref "C7") (pin "2") (pinfunction "2_2") (pintype "passive"))
      (node (ref "C79") (pin "2") (pinfunction "2_2") (pintype "passive"))
      (node (ref "C8") (pin "2") (pinfunction "2_2") (pintype "passive"))
      (node (ref "C80") (pin "2") (pinfunction "2_2") (pintype "passive"))
      (node (ref "C81") (pin "2") (pinfunction "2_2") (pintype "passive"))
      (node (ref "C82") (pin "2") (pinfunction "2_2") (pintype "passive"))
      (node (ref "C9") (pin "2") (pinfunction "2_2") (pintype "passive"))
      (node (ref "FB1") (pin "2") (pinfunction "2_2") (pintype "passive"))
      (node (ref "FB3") (pin "2") (pinfunction "2_2") (pintype "passive"))
      (node (ref "J5") (pin "24") (pinfunction "24_24") (pintype "bidirectional"))
      (node (ref "J5") (pin "25") (pinfunction "25_25") (pintype "bidirectional"))
      (node (ref "R10") (pin "2") (pinfunction "2_2") (pintype "passive"))
      (node (ref "R12") (pin "2") (pinfunction "2_2") (pintype "passive"))
      (node (ref "R14") (pin "2") (pinfunction "2_2") (pintype "passive"))
      (node (ref "R15") (pin "2") (pinfunction "2_2") (pintype "passive"))
      (node (ref "R16") (pin "2") (pinfunction "2_2") (pintype "passive"))
      (node (ref "R2") (pin "2") (pinfunction "2_2") (pintype "passive"))
      (node (ref "R22") (pin "2") (pinfunction "2_2") (pintype "passive"))
      (node (ref "R30") (pin "2") (pinfunction "2_2") (pintype "passive"))
      (node (ref "R31") (pin "2") (pinfunction "2_2") (pintype "passive"))
      (node (ref "R32") (pin "2") (pinfunction "2_2") (pintype "passive"))
      (node (ref "R48") (pin "2") (pinfunction "2_2") (pintype "passive"))
      (node (ref "R49") (pin "2") (pinfunction "2_2") (pintype "passive"))
      (node (ref "R53") (pin "2") (pinfunction "2_2") (pintype "passive"))
      (node (ref "R54") (pin "2") (pinfunction "2_2") (pintype "passive"))
      (node (ref "RJ1") (pin "4") (pinfunction "4_4") (pintype "passive"))
      (node (ref "RJ1") (pin "5") (pinfunction "5_5") (pintype "passive"))
      (node (ref "TP1") (pin "PAD") (pinfunction "2_PAD") (pintype "passive"))
      (node (ref "U1") (pin "6") (pinfunction "6_6") (pintype "bidirectional"))
      (node (ref "U10") (pin "15") (pinfunction "VCC_15") (pintype "bidirectional"))
      (node (ref "U10") (pin "3") (pinfunction "VCCIO_3") (pintype "bidirectional"))
      (node (ref "U11") (pin "1") (pinfunction "1_1") (pintype "bidirectional"))
      (node (ref "U12") (pin "6") (pinfunction "6_6") (pintype "bidirectional"))
      (node (ref "U13") (pin "6") (pinfunction "6_6") (pintype "bidirectional"))
      (node (ref "U14") (pin "6") (pinfunction "6_6") (pintype "bidirectional"))
      (node (ref "U15") (pin "1") (pinfunction "1_1") (pintype "bidirectional"))
      (node (ref "U17") (pin "5") (pinfunction "VCC_5") (pintype "bidirectional"))
      (node (ref "U2") (pin "1") (pinfunction "1_1") (pintype "bidirectional"))
      (node (ref "U20") (pin "5") (pinfunction "VCC_5") (pintype "bidirectional"))
      (node (ref "U21") (pin "6") (pinfunction "6_6") (pintype "bidirectional"))
      (node (ref "U22") (pin "6") (pinfunction "6_6") (pintype "bidirectional"))
      (node (ref "U23") (pin "6") (pinfunction "6_6") (pintype "bidirectional"))
      (node (ref "U24") (pin "6") (pinfunction "6_6") (pintype "bidirectional"))
      (node (ref "U25") (pin "1") (pinfunction "1_1") (pintype "bidirectional"))
      (node (ref "U26") (pin "1") (pinfunction "1_1") (pintype "bidirectional"))
      (node (ref "U27") (pin "1") (pinfunction "1_1") (pintype "bidirectional"))
      (node (ref "U28") (pin "1") (pinfunction "1_1") (pintype "bidirectional"))
      (node (ref "U3") (pin "6") (pinfunction "VCC_6") (pintype "bidirectional"))
      (node (ref "U30") (pin "1") (pinfunction "1_1") (pintype "bidirectional"))
      (node (ref "U4") (pin "19") (pinfunction "VDD33IO_19") (pintype "bidirectional"))
      (node (ref "U4") (pin "27") (pinfunction "VDD33IO_27") (pintype "bidirectional"))
      (node (ref "U4") (pin "33") (pinfunction "VDD33IO_33") (pintype "bidirectional"))
      (node (ref "U4") (pin "39") (pinfunction "VDD33IO_39") (pintype "bidirectional"))
      (node (ref "U4") (pin "40") (pinfunction "TEST3_40") (pintype "bidirectional"))
      (node (ref "U4") (pin "46") (pinfunction "VDD33IO_46") (pintype "bidirectional"))
      (node (ref "U5") (pin "6") (pinfunction "6_6") (pintype "bidirectional"))
      (node (ref "U6") (pin "6") (pinfunction "6_6") (pintype "bidirectional"))
      (node (ref "U7") (pin "6") (pinfunction "6_6") (pintype "bidirectional"))
      (node (ref "U8") (pin "1") (pinfunction "1_1") (pintype "bidirectional"))
      (node (ref "U9") (pin "8") (pinfunction "8_8") (pintype "bidirectional"))
      (node (ref "VR1") (pin "P$1") (pinfunction "TAB_P$1") (pintype "bidirectional"))
    )
    (net (code "3") (name "+5V") (class "Default")
      (node (ref "C3") (pin "POS") (pinfunction "POS_POS") (pintype "passive"))
      (node (ref "J18") (pin "6") (pinfunction "6_6") (pintype "bidirectional"))
      (node (ref "J6") (pin "6") (pinfunction "6_6") (pintype "passive"))
      (node (ref "TB1") (pin "2") (pinfunction "2_2") (pintype "passive"))
      (node (ref "TP2") (pin "PAD") (pinfunction "2_PAD") (pintype "passive"))
      (node (ref "U18") (pin "7") (pinfunction "IN_7") (pintype "bidirectional"))
      (node (ref "U19") (pin "7") (pinfunction "IN_7") (pintype "bidirectional"))
      (node (ref "VR1") (pin "3") (pinfunction "IN_3") (pintype "bidirectional"))
    )
    (net (code "4") (name "+24V") (class "Default")
      (node (ref "J16") (pin "1") (pinfunction "1_1") (pintype "passive"))
      (node (ref "J17") (pin "1") (pinfunction "1_1") (pintype "passive"))
      (node (ref "J18") (pin "1") (pinfunction "1_1") (pintype "bidirectional"))
      (node (ref "J6") (pin "1") (pinfunction "1_1") (pintype "passive"))
      (node (ref "R3") (pin "2") (pinfunction "2_2") (pintype "passive"))
      (node (ref "TB1") (pin "1") (pinfunction "1_1") (pintype "passive"))
      (node (ref "TP3") (pin "PAD") (pinfunction "2_PAD") (pintype "passive"))
    )
    (net (code "5") (name "74DIR") (class "Default")
      (node (ref "J20") (pin "25") (pinfunction "GP165_25") (pintype "bidirectional"))
      (node (ref "U30") (pin "3") (pinfunction "3_3") (pintype "bidirectional"))
    )
    (net (code "6") (name "74DIRO") (class "Default")
      (node (ref "U1") (pin "5") (pinfunction "5_5") (pintype "bidirectional"))
      (node (ref "U2") (pin "5") (pinfunction "5_5") (pintype "bidirectional"))
      (node (ref "U23") (pin "5") (pinfunction "5_5") (pintype "bidirectional"))
      (node (ref "U24") (pin "5") (pinfunction "5_5") (pintype "bidirectional"))
      (node (ref "U25") (pin "5") (pinfunction "5_5") (pintype "bidirectional"))
      (node (ref "U26") (pin "5") (pinfunction "5_5") (pintype "bidirectional"))
      (node (ref "U27") (pin "5") (pinfunction "5_5") (pintype "bidirectional"))
      (node (ref "U28") (pin "5") (pinfunction "5_5") (pintype "bidirectional"))
      (node (ref "U30") (pin "4") (pinfunction "4_4") (pintype "bidirectional"))
      (node (ref "U5") (pin "5") (pinfunction "5_5") (pintype "bidirectional"))
      (node (ref "U6") (pin "5") (pinfunction "5_5") (pintype "bidirectional"))
      (node (ref "U7") (pin "5") (pinfunction "5_5") (pintype "bidirectional"))
      (node (ref "U8") (pin "5") (pinfunction "5_5") (pintype "bidirectional"))
    )
    (net (code "7") (name "A") (class "Default")
      (node (ref "J16") (pin "4") (pinfunction "4_4") (pintype "passive"))
      (node (ref "J17") (pin "4") (pinfunction "4_4") (pintype "passive"))
      (node (ref "J18") (pin "4") (pinfunction "4_4") (pintype "bidirectional"))
      (node (ref "J6") (pin "4") (pinfunction "4_4") (pintype "passive"))
      (node (ref "R50") (pin "2") (pinfunction "2_2") (pintype "passive"))
      (node (ref "R51") (pin "1") (pinfunction "1_1") (pintype "passive"))
      (node (ref "U9") (pin "6") (pinfunction "6_6") (pintype "bidirectional"))
    )
    (net (code "8") (name "B") (class "Default")
      (node (ref "J16") (pin "5") (pinfunction "5_5") (pintype "passive"))
      (node (ref "J17") (pin "5") (pinfunction "5_5") (pintype "passive"))
      (node (ref "J18") (pin "5") (pinfunction "5_5") (pintype "bidirectional"))
      (node (ref "J6") (pin "5") (pinfunction "5_5") (pintype "passive"))
      (node (ref "R49") (pin "1") (pinfunction "1_1") (pintype "passive"))
      (node (ref "R51") (pin "2") (pinfunction "2_2") (pintype "passive"))
      (node (ref "U9") (pin "7") (pinfunction "7_7") (pintype "bidirectional"))
    )
    (net (code "9") (name "D0O") (class "Default")
      (node (ref "J20") (pin "52") (pinfunction "GP40_52") (pintype "bidirectional"))
      (node (ref "U24") (pin "4") (pinfunction "4_4") (pintype "bidirectional"))
    )
    (net (code "10") (name "D1O") (class "Default")
      (node (ref "J20") (pin "54") (pinfunction "GP41_54") (pintype "bidirectional"))
      (node (ref "U23") (pin "4") (pinfunction "4_4") (pintype "bidirectional"))
    )
    (net (code "11") (name "D2O") (class "Default")
      (node (ref "J20") (pin "50") (pinfunction "GP42_50") (pintype "bidirectional"))
      (node (ref "U7") (pin "4") (pinfunction "4_4") (pintype "bidirectional"))
    )
    (net (code "12") (name "D3O") (class "Default")
      (node (ref "J20") (pin "56") (pinfunction "GP43_56") (pintype "bidirectional"))
      (node (ref "U8") (pin "4") (pinfunction "4_4") (pintype "bidirectional"))
    )
    (net (code "13") (name "D4O") (class "Default")
      (node (ref "J20") (pin "24") (pinfunction "GP44_24") (pintype "bidirectional"))
      (node (ref "U6") (pin "4") (pinfunction "4_4") (pintype "bidirectional"))
    )
    (net (code "14") (name "D5O") (class "Default")
      (node (ref "J20") (pin "26") (pinfunction "GP45_26") (pintype "bidirectional"))
      (node (ref "U5") (pin "4") (pinfunction "4_4") (pintype "bidirectional"))
    )
    (net (code "15") (name "D6O") (class "Default")
      (node (ref "J20") (pin "28") (pinfunction "GP46_28") (pintype "bidirectional"))
      (node (ref "U1") (pin "4") (pinfunction "4_4") (pintype "bidirectional"))
    )
    (net (code "16") (name "D7O") (class "Default")
      (node (ref "J20") (pin "30") (pinfunction "GP47_30") (pintype "bidirectional"))
      (node (ref "U2") (pin "4") (pinfunction "4_4") (pintype "bidirectional"))
    )
    (net (code "17") (name "DI2") (class "Default")
      (node (ref "J20") (pin "46") (pinfunction "GP131_46") (pintype "bidirectional"))
      (node (ref "U13") (pin "3") (pinfunction "3_3") (pintype "bidirectional"))
    )
    (net (code "18") (name "DI2O") (class "Default")
      (node (ref "U13") (pin "4") (pinfunction "4_4") (pintype "bidirectional"))
      (node (ref "U9") (pin "4") (pinfunction "4_4") (pintype "bidirectional"))
    )
    (net (code "19") (name "EECLK") (class "Default")
      (node (ref "U3") (pin "4") (pinfunction "CLK_4") (pintype "bidirectional"))
      (node (ref "U4") (pin "23") (pinfunction "EECLK_23") (pintype "bidirectional"))
    )
    (net (code "20") (name "EECS") (class "Default")
      (node (ref "U3") (pin "5") (pinfunction "CS_5") (pintype "bidirectional"))
      (node (ref "U4") (pin "24") (pinfunction "EECS_24") (pintype "bidirectional"))
    )
    (net (code "21") (name "EEDI") (class "Default")
      (node (ref "U3") (pin "1") (pinfunction "DO_1") (pintype "bidirectional"))
      (node (ref "U4") (pin "26") (pinfunction "EEDI_26") (pintype "bidirectional"))
    )
    (net (code "22") (name "EEDO") (class "Default")
      (node (ref "U3") (pin "3") (pinfunction "DI_3") (pintype "bidirectional"))
      (node (ref "U4") (pin "25") (pinfunction "EEDO_25") (pintype "bidirectional"))
    )
    (net (code "23") (name "EEEN") (class "Default")
      (node (ref "J20") (pin "48") (pinfunction "GP14_48") (pintype "bidirectional"))
      (node (ref "U22") (pin "3") (pinfunction "3_3") (pintype "bidirectional"))
    )
    (net (code "24") (name "EEENO") (class "Default")
      (node (ref "U17") (pin "1") (pinfunction "A_1") (pintype "bidirectional"))
      (node (ref "U22") (pin "4") (pinfunction "4_4") (pintype "bidirectional"))
    )
    (net (code "25") (name "EE_N") (class "Default")
      (node (ref "J16") (pin "8") (pinfunction "8_8") (pintype "passive"))
      (node (ref "U4") (pin "3") (pinfunction "USBDM3_3") (pintype "bidirectional"))
    )
    (net (code "26") (name "EE_P") (class "Default")
      (node (ref "J16") (pin "7") (pinfunction "7_7") (pintype "passive"))
      (node (ref "U4") (pin "4") (pinfunction "USBDP3_4") (pintype "bidirectional"))
    )
    (net (code "27") (name "ESTOPIN") (class "Default")
      (node (ref "J2") (pin "1") (pinfunction "1_1") (pintype "passive"))
      (node (ref "R2") (pin "1") (pinfunction "1_1") (pintype "passive"))
    )
    (net (code "28") (name "EXRES") (class "Default")
      (node (ref "R13") (pin "2") (pinfunction "2_2") (pintype "passive"))
      (node (ref "U4") (pin "50") (pinfunction "EXRES_50") (pintype "bidirectional"))
    )
    (net (code "29") (name "GND") (class "Default")
      (node (ref "C1") (pin "1") (pinfunction "1_1") (pintype "passive"))
      (node (ref "C10") (pin "1") (pinfunction "1_1") (pintype "passive"))
      (node (ref "C11") (pin "1") (pinfunction "1_1") (pintype "passive"))
      (node (ref "C12") (pin "1") (pinfunction "1_1") (pintype "passive"))
      (node (ref "C13") (pin "1") (pinfunction "1_1") (pintype "passive"))
      (node (ref "C14") (pin "1") (pinfunction "1_1") (pintype "passive"))
      (node (ref "C15") (pin "1") (pinfunction "1_1") (pintype "passive"))
      (node (ref "C16") (pin "1") (pinfunction "1_1") (pintype "passive"))
      (node (ref "C17") (pin "1") (pinfunction "1_1") (pintype "passive"))
      (node (ref "C18") (pin "1") (pinfunction "1_1") (pintype "passive"))
      (node (ref "C19") (pin "1") (pinfunction "1_1") (pintype "passive"))
      (node (ref "C2") (pin "1") (pinfunction "1_1") (pintype "passive"))
      (node (ref "C20") (pin "1") (pinfunction "1_1") (pintype "passive"))
      (node (ref "C21") (pin "1") (pinfunction "1_1") (pintype "passive"))
      (node (ref "C22") (pin "1") (pinfunction "1_1") (pintype "passive"))
      (node (ref "C23") (pin "1") (pinfunction "1_1") (pintype "passive"))
      (node (ref "C24") (pin "1") (pinfunction "1_1") (pintype "passive"))
      (node (ref "C25") (pin "1") (pinfunction "1_1") (pintype "passive"))
      (node (ref "C26") (pin "1") (pinfunction "1_1") (pintype "passive"))
      (node (ref "C27") (pin "1") (pinfunction "1_1") (pintype "passive"))
      (node (ref "C28") (pin "1") (pinfunction "1_1") (pintype "passive"))
      (node (ref "C29") (pin "1") (pinfunction "1_1") (pintype "passive"))
      (node (ref "C3") (pin "NEG") (pinfunction "NEG_NEG") (pintype "passive"))
      (node (ref "C30") (pin "1") (pinfunction "1_1") (pintype "passive"))
      (node (ref "C31") (pin "1") (pinfunction "1_1") (pintype "passive"))
      (node (ref "C32") (pin "1") (pinfunction "1_1") (pintype "passive"))
      (node (ref "C33") (pin "1") (pinfunction "1_1") (pintype "passive"))
      (node (ref "C34") (pin "1") (pinfunction "1_1") (pintype "passive"))
      (node (ref "C35") (pin "1") (pinfunction "1_1") (pintype "passive"))
      (node (ref "C36") (pin "1") (pinfunction "1_1") (pintype "passive"))
      (node (ref "C37") (pin "1") (pinfunction "1_1") (pintype "passive"))
      (node (ref "C38") (pin "1") (pinfunction "1_1") (pintype "passive"))
      (node (ref "C39") (pin "1") (pinfunction "1_1") (pintype "passive"))
      (node (ref "C4") (pin "NEG") (pinfunction "NEG_NEG") (pintype "passive"))
      (node (ref "C40") (pin "1") (pinfunction "1_1") (pintype "passive"))
      (node (ref "C41") (pin "1") (pinfunction "1_1") (pintype "passive"))
      (node (ref "C42") (pin "1") (pinfunction "1_1") (pintype "passive"))
      (node (ref "C43") (pin "1") (pinfunction "1_1") (pintype "passive"))
      (node (ref "C44") (pin "1") (pinfunction "1_1") (pintype "passive"))
      (node (ref "C45") (pin "1") (pinfunction "1_1") (pintype "passive"))
      (node (ref "C46") (pin "1") (pinfunction "1_1") (pintype "passive"))
      (node (ref "C47") (pin "1") (pinfunction "1_1") (pintype "passive"))
      (node (ref "C48") (pin "1") (pinfunction "1_1") (pintype "passive"))
      (node (ref "C49") (pin "1") (pinfunction "1_1") (pintype "passive"))
      (node (ref "C5") (pin "1") (pinfunction "1_1") (pintype "passive"))
      (node (ref "C6") (pin "1") (pinfunction "1_1") (pintype "passive"))
      (node (ref "C60") (pin "1") (pinfunction "1_1") (pintype "passive"))
      (node (ref "C61") (pin "1") (pinfunction "1_1") (pintype "passive"))
      (node (ref "C7") (pin "1") (pinfunction "1_1") (pintype "passive"))
      (node (ref "C73") (pin "1") (pinfunction "1_1") (pintype "passive"))
      (node (ref "C74") (pin "1") (pinfunction "1_1") (pintype "passive"))
      (node (ref "C77") (pin "1") (pinfunction "1_1") (pintype "passive"))
      (node (ref "C78") (pin "1") (pinfunction "1_1") (pintype "passive"))
      (node (ref "C79") (pin "1") (pinfunction "1_1") (pintype "passive"))
      (node (ref "C8") (pin "1") (pinfunction "1_1") (pintype "passive"))
      (node (ref "C80") (pin "1") (pinfunction "1_1") (pintype "passive"))
      (node (ref "C81") (pin "1") (pinfunction "1_1") (pintype "passive"))
      (node (ref "C82") (pin "1") (pinfunction "1_1") (pintype "passive"))
      (node (ref "C83") (pin "1") (pinfunction "1_1") (pintype "passive"))
      (node (ref "C84") (pin "1") (pinfunction "1_1") (pintype "passive"))
      (node (ref "C85") (pin "1") (pinfunction "1_1") (pintype "passive"))
      (node (ref "C9") (pin "1") (pinfunction "1_1") (pintype "passive"))
      (node (ref "J1") (pin "2") (pinfunction "2_2") (pintype "passive"))
      (node (ref "J1") (pin "4") (pinfunction "4_4") (pintype "passive"))
      (node (ref "J16") (pin "3") (pinfunction "3_3") (pintype "passive"))
      (node (ref "J17") (pin "3") (pinfunction "3_3") (pintype "passive"))
      (node (ref "J18") (pin "3") (pinfunction "3_3") (pintype "bidirectional"))
      (node (ref "J20") (pin "1") (pinfunction "GND_1") (pintype "bidirectional"))
      (node (ref "J20") (pin "11") (pinfunction "GND_11") (pintype "bidirectional"))
      (node (ref "J20") (pin "13") (pinfunction "GND_13") (pintype "bidirectional"))
      (node (ref "J20") (pin "15") (pinfunction "GND_15") (pintype "bidirectional"))
      (node (ref "J20") (pin "5") (pinfunction "GND_5") (pintype "bidirectional"))
      (node (ref "J20") (pin "9") (pinfunction "GND_9") (pintype "bidirectional"))
      (node (ref "J3") (pin "4") (pinfunction "GND_4") (pintype "bidirectional"))
      (node (ref "J5") (pin "26") (pinfunction "26_26") (pintype "bidirectional"))
      (node (ref "J5") (pin "27") (pinfunction "27_27") (pintype "bidirectional"))
      (node (ref "J6") (pin "3") (pinfunction "3_3") (pintype "passive"))
      (node (ref "J7") (pin "4") (pinfunction "4_4") (pintype "passive"))
      (node (ref "LED10") (pin "C") (pinfunction "C_C") (pintype "passive"))
      (node (ref "LED12") (pin "C") (pinfunction "C_C") (pintype "passive"))
      (node (ref "LED13") (pin "C") (pinfunction "C_C") (pintype "passive"))
      (node (ref "LED14") (pin "C") (pinfunction "C_C") (pintype "passive"))
      (node (ref "R1") (pin "1") (pinfunction "1_1") (pintype "passive"))
      (node (ref "R13") (pin "1") (pinfunction "1_1") (pintype "passive"))
      (node (ref "R33") (pin "2") (pinfunction "2_2") (pintype "passive"))
      (node (ref "R34") (pin "2") (pinfunction "2_2") (pintype "passive"))
      (node (ref "R35") (pin "1") (pinfunction "1_1") (pintype "passive"))
      (node (ref "R50") (pin "1") (pinfunction "1_1") (pintype "passive"))
      (node (ref "RJ1") (pin "8") (pinfunction "GND_8") (pintype "passive"))
      (node (ref "RJ1") (pin "SHLD0") (pinfunction "SHLD0_SHLD0") (pintype "passive"))
      (node (ref "RJ1") (pin "SHLD1") (pinfunction "SHLD1_SHLD1") (pintype "passive"))
      (node (ref "TB1") (pin "3") (pinfunction "3_3") (pintype "passive"))
      (node (ref "TP4") (pin "PAD") (pinfunction "2_PAD") (pintype "passive"))
      (node (ref "U1") (pin "2") (pinfunction "2_2") (pintype "bidirectional"))
      (node (ref "U10") (pin "16") (pinfunction "GND_16") (pintype "bidirectional"))
      (node (ref "U10") (pin "6") (pinfunction "GND_6") (pintype "bidirectional"))
      (node (ref "U11") (pin "2") (pinfunction "2_2") (pintype "bidirectional"))
      (node (ref "U11") (pin "5") (pinfunction "5_5") (pintype "bidirectional"))
      (node (ref "U12") (pin "2") (pinfunction "2_2") (pintype "bidirectional"))
      (node (ref "U12") (pin "5") (pinfunction "5_5") (pintype "bidirectional"))
      (node (ref "U13") (pin "2") (pinfunction "2_2") (pintype "bidirectional"))
      (node (ref "U13") (pin "5") (pinfunction "5_5") (pintype "bidirectional"))
      (node (ref "U14") (pin "2") (pinfunction "2_2") (pintype "bidirectional"))
      (node (ref "U14") (pin "5") (pinfunction "5_5") (pintype "bidirectional"))
      (node (ref "U15") (pin "2") (pinfunction "2_2") (pintype "bidirectional"))
      (node (ref "U15") (pin "5") (pinfunction "5_5") (pintype "bidirectional"))
      (node (ref "U17") (pin "3") (pinfunction "GND_3") (pintype "bidirectional"))
      (node (ref "U18") (pin "6") (pinfunction "GND_6") (pintype "bidirectional"))
      (node (ref "U19") (pin "6") (pinfunction "GND_6") (pintype "bidirectional"))
      (node (ref "U2") (pin "2") (pinfunction "2_2") (pintype "bidirectional"))
      (node (ref "U20") (pin "3") (pinfunction "GND_3") (pintype "bidirectional"))
      (node (ref "U21") (pin "2") (pinfunction "2_2") (pintype "bidirectional"))
      (node (ref "U21") (pin "5") (pinfunction "5_5") (pintype "bidirectional"))
      (node (ref "U22") (pin "2") (pinfunction "2_2") (pintype "bidirectional"))
      (node (ref "U22") (pin "5") (pinfunction "5_5") (pintype "bidirectional"))
      (node (ref "U23") (pin "2") (pinfunction "2_2") (pintype "bidirectional"))
      (node (ref "U24") (pin "2") (pinfunction "2_2") (pintype "bidirectional"))
      (node (ref "U25") (pin "2") (pinfunction "2_2") (pintype "bidirectional"))
      (node (ref "U26") (pin "2") (pinfunction "2_2") (pintype "bidirectional"))
      (node (ref "U27") (pin "2") (pinfunction "2_2") (pintype "bidirectional"))
      (node (ref "U28") (pin "2") (pinfunction "2_2") (pintype "bidirectional"))
      (node (ref "U3") (pin "2") (pinfunction "VSS_2") (pintype "bidirectional"))
      (node (ref "U30") (pin "2") (pinfunction "2_2") (pintype "bidirectional"))
      (node (ref "U30") (pin "5") (pinfunction "5_5") (pintype "bidirectional"))
      (node (ref "U4") (pin "34") (pinfunction "TEST2_34") (pintype "bidirectional"))
      (node (ref "U4") (pin "44") (pinfunction "CLK24_EN_44") (pintype "bidirectional"))
      (node (ref "U4") (pin "PAD") (pinfunction "PAD_PAD") (pintype "bidirectional"))
      (node (ref "U5") (pin "2") (pinfunction "2_2") (pintype "bidirectional"))
      (node (ref "U6") (pin "2") (pinfunction "2_2") (pintype "bidirectional"))
      (node (ref "U7") (pin "2") (pinfunction "2_2") (pintype "bidirectional"))
      (node (ref "U8") (pin "2") (pinfunction "2_2") (pintype "bidirectional"))
      (node (ref "U9") (pin "5") (pinfunction "5_5") (pintype "bidirectional"))
      (node (ref "VR1") (pin "1") (pinfunction "GND_1") (pintype "bidirectional"))
    )
    (net (code "30") (name "LCD_BL") (class "Default")
      (node (ref "J5") (pin "23") (pinfunction "23_23") (pintype "bidirectional"))
    )
    (net (code "31") (name "LCD_CLK") (class "Default")
      (node (ref "J5") (pin "34") (pinfunction "34_34") (pintype "bidirectional"))
    )
    (net (code "32") (name "LCD_CS") (class "Default")
      (node (ref "J5") (pin "1") (pinfunction "1_1") (pintype "bidirectional"))
      (node (ref "U25") (pin "3") (pinfunction "3_3") (pintype "bidirectional"))
    )
    (net (code "33") (name "LCD_D0") (class "Default")
      (node (ref "J5") (pin "6") (pinfunction "6_6") (pintype "bidirectional"))
      (node (ref "U24") (pin "3") (pinfunction "3_3") (pintype "bidirectional"))
    )
    (net (code "34") (name "LCD_D1") (class "Default")
      (node (ref "J5") (pin "7") (pinfunction "7_7") (pintype "bidirectional"))
      (node (ref "U23") (pin "3") (pinfunction "3_3") (pintype "bidirectional"))
    )
    (net (code "35") (name "LCD_D2") (class "Default")
      (node (ref "J5") (pin "8") (pinfunction "8_8") (pintype "bidirectional"))
      (node (ref "U7") (pin "3") (pinfunction "3_3") (pintype "bidirectional"))
    )
    (net (code "36") (name "LCD_D3") (class "Default")
      (node (ref "J5") (pin "9") (pinfunction "9_9") (pintype "bidirectional"))
      (node (ref "U8") (pin "3") (pinfunction "3_3") (pintype "bidirectional"))
    )
    (net (code "37") (name "LCD_D4") (class "Default")
      (node (ref "J5") (pin "10") (pinfunction "10_10") (pintype "bidirectional"))
      (node (ref "U6") (pin "3") (pinfunction "3_3") (pintype "bidirectional"))
    )
    (net (code "38") (name "LCD_D5") (class "Default")
      (node (ref "J5") (pin "11") (pinfunction "11_11") (pintype "bidirectional"))
      (node (ref "U5") (pin "3") (pinfunction "3_3") (pintype "bidirectional"))
    )
    (net (code "39") (name "LCD_D6") (class "Default")
      (node (ref "J5") (pin "12") (pinfunction "12_12") (pintype "bidirectional"))
      (node (ref "U1") (pin "3") (pinfunction "3_3") (pintype "bidirectional"))
    )
    (net (code "40") (name "LCD_D7") (class "Default")
      (node (ref "J5") (pin "13") (pinfunction "13_13") (pintype "bidirectional"))
      (node (ref "U2") (pin "3") (pinfunction "3_3") (pintype "bidirectional"))
    )
    (net (code "41") (name "LCD_D8") (class "Default")
      (node (ref "J5") (pin "14") (pinfunction "14_14") (pintype "bidirectional"))
    )
    (net (code "42") (name "LCD_D9") (class "Default")
      (node (ref "J5") (pin "15") (pinfunction "15_15") (pintype "bidirectional"))
    )
    (net (code "43") (name "LCD_D10") (class "Default")
      (node (ref "J5") (pin "16") (pinfunction "16_16") (pintype "bidirectional"))
    )
    (net (code "44") (name "LCD_D11") (class "Default")
      (node (ref "J5") (pin "17") (pinfunction "17_17") (pintype "bidirectional"))
    )
    (net (code "45") (name "LCD_D12") (class "Default")
      (node (ref "J5") (pin "18") (pinfunction "18_18") (pintype "bidirectional"))
    )
    (net (code "46") (name "LCD_D13") (class "Default")
      (node (ref "J5") (pin "19") (pinfunction "19_19") (pintype "bidirectional"))
    )
    (net (code "47") (name "LCD_D14") (class "Default")
      (node (ref "J5") (pin "20") (pinfunction "20_20") (pintype "bidirectional"))
    )
    (net (code "48") (name "LCD_D15") (class "Default")
      (node (ref "J5") (pin "21") (pinfunction "21_21") (pintype "bidirectional"))
    )
    (net (code "49") (name "LCD_FCS") (class "Default")
      (node (ref "J5") (pin "32") (pinfunction "32_32") (pintype "bidirectional"))
    )
    (net (code "50") (name "LCD_MISO") (class "Default")
      (node (ref "J5") (pin "29") (pinfunction "29_29") (pintype "bidirectional"))
    )
    (net (code "51") (name "LCD_MOSI") (class "Default")
      (node (ref "J5") (pin "30") (pinfunction "30_30") (pintype "bidirectional"))
    )
    (net (code "52") (name "LCD_PEN") (class "Default")
      (node (ref "J5") (pin "31") (pinfunction "31_31") (pintype "bidirectional"))
    )
    (net (code "53") (name "LCD_RD") (class "Default")
      (node (ref "J5") (pin "4") (pinfunction "4_4") (pintype "bidirectional"))
      (node (ref "U27") (pin "3") (pinfunction "3_3") (pintype "bidirectional"))
    )
    (net (code "54") (name "LCD_RS") (class "Default")
      (node (ref "J5") (pin "2") (pinfunction "2_2") (pintype "bidirectional"))
      (node (ref "U28") (pin "3") (pinfunction "3_3") (pintype "bidirectional"))
    )
    (net (code "55") (name "LCD_RST") (class "Default")
      (node (ref "J5") (pin "5") (pinfunction "5_5") (pintype "bidirectional"))
    )
    (net (code "56") (name "LCD_SDCS") (class "Default")
      (node (ref "J5") (pin "22") (pinfunction "22_22") (pintype "bidirectional"))
    )
    (net (code "57") (name "LCD_TCS") (class "Default")
      (node (ref "J5") (pin "33") (pinfunction "33_33") (pintype "bidirectional"))
    )
    (net (code "58") (name "LCD_WR") (class "Default")
      (node (ref "J5") (pin "3") (pinfunction "3_3") (pintype "bidirectional"))
      (node (ref "U26") (pin "3") (pinfunction "3_3") (pintype "bidirectional"))
    )
    (net (code "59") (name "LCSO") (class "Default")
      (node (ref "J20") (pin "39") (pinfunction "GP183_39") (pintype "bidirectional"))
      (node (ref "U25") (pin "4") (pinfunction "4_4") (pintype "bidirectional"))
    )
    (net (code "60") (name "LED_DUPLEX") (class "Default")
      (node (ref "LED11") (pin "C") (pinfunction "C_C") (pintype "passive"))
      (node (ref "U4") (pin "20") (pinfunction "GPIO0_20") (pintype "bidirectional"))
    )
    (net (code "61") (name "LED_SPEED") (class "Default")
      (node (ref "RJ1") (pin "12") (pinfunction "LED_Y+_12") (pintype "passive"))
      (node (ref "U4") (pin "22") (pinfunction "GPIO2_22") (pintype "bidirectional"))
    )
    (net (code "62") (name "LED_TXRX") (class "Default")
      (node (ref "RJ1") (pin "9") (pinfunction "LED_G+_9") (pintype "passive"))
      (node (ref "U4") (pin "21") (pinfunction "GPIO1_21") (pintype "bidirectional"))
    )
    (net (code "63") (name "LRDO") (class "Default")
      (node (ref "J20") (pin "37") (pinfunction "GP182_37") (pintype "bidirectional"))
      (node (ref "U27") (pin "4") (pinfunction "4_4") (pintype "bidirectional"))
    )
    (net (code "64") (name "LRSO") (class "Default")
      (node (ref "J20") (pin "34") (pinfunction "GP49_34") (pintype "bidirectional"))
      (node (ref "U28") (pin "4") (pinfunction "4_4") (pintype "bidirectional"))
    )
    (net (code "65") (name "LWRO") (class "Default")
      (node (ref "J20") (pin "32") (pinfunction "GP48_32") (pintype "bidirectional"))
      (node (ref "U26") (pin "4") (pinfunction "4_4") (pintype "bidirectional"))
    )
    (net (code "66") (name "NC") (class "Default")
      (node (ref "J5") (pin "28") (pinfunction "28_28") (pintype "bidirectional"))
    )
    (net (code "67") (name "Net-(C78-Pad2)") (class "Default")
      (node (ref "C78") (pin "2") (pinfunction "2_2") (pintype "passive"))
      (node (ref "FB3") (pin "1") (pinfunction "1_1") (pintype "passive"))
      (node (ref "J7") (pin "1") (pinfunction "1_1") (pintype "passive"))
    )
    (net (code "68") (name "Net-(J1-Pad3)") (class "Default")
      (node (ref "J1") (pin "3") (pinfunction "3_3") (pintype "passive"))
      (node (ref "R3") (pin "1") (pinfunction "1_1") (pintype "passive"))
    )
    (net (code "69") (name "Net-(J2-Pad2)") (class "Default")
      (node (ref "J2") (pin "2") (pinfunction "2_2") (pintype "passive"))
      (node (ref "R1") (pin "2") (pinfunction "2_2") (pintype "passive"))
    )
    (net (code "70") (name "Net-(J20-1.8V)") (class "Default")
      (node (ref "J20") (pin "12") (pinfunction "1.8V_12") (pintype "bidirectional"))
      (node (ref "R57") (pin "2") (pinfunction "2_2") (pintype "passive"))
      (node (ref "R58") (pin "2") (pinfunction "2_2") (pintype "passive"))
    )
    (net (code "71") (name "Net-(J20-DCIN)") (class "Default")
      (node (ref "J20") (pin "14") (pinfunction "DCIN_14") (pintype "bidirectional"))
      (node (ref "J20") (pin "2") (pinfunction "VSYS_2") (pintype "bidirectional"))
      (node (ref "J20") (pin "4") (pinfunction "VSYS_4") (pintype "bidirectional"))
      (node (ref "J20") (pin "6") (pinfunction "VSYS_6") (pintype "bidirectional"))
      (node (ref "R15") (pin "1") (pinfunction "1_1") (pintype "passive"))
      (node (ref "R16") (pin "1") (pinfunction "1_1") (pintype "passive"))
    )
    (net (code "72") (name "Net-(LED8-PadA)") (class "Default")
      (node (ref "LED8") (pin "A") (pinfunction "A_A") (pintype "passive"))
      (node (ref "R53") (pin "1") (pinfunction "1_1") (pintype "passive"))
    )
    (net (code "73") (name "Net-(LED9-PadA)") (class "Default")
      (node (ref "LED9") (pin "A") (pinfunction "A_A") (pintype "passive"))
      (node (ref "R54") (pin "1") (pinfunction "1_1") (pintype "passive"))
    )
    (net (code "74") (name "Net-(LED10-PadA)") (class "Default")
      (node (ref "LED10") (pin "A") (pinfunction "A_A") (pintype "passive"))
      (node (ref "R37") (pin "1") (pinfunction "1_1") (pintype "passive"))
    )
    (net (code "75") (name "Net-(LED11-PadA)") (class "Default")
      (node (ref "LED11") (pin "A") (pinfunction "A_A") (pintype "passive"))
      (node (ref "R10") (pin "1") (pinfunction "1_1") (pintype "passive"))
    )
    (net (code "76") (name "Net-(LED12-PadA)") (class "Default")
      (node (ref "LED12") (pin "A") (pinfunction "A_A") (pintype "passive"))
      (node (ref "R52") (pin "1") (pinfunction "1_1") (pintype "passive"))
    )
    (net (code "77") (name "Net-(LED13-PadA)") (class "Default")
      (node (ref "LED13") (pin "A") (pinfunction "A_A") (pintype "passive"))
      (node (ref "R55") (pin "1") (pinfunction "1_1") (pintype "passive"))
    )
    (net (code "78") (name "Net-(LED14-PadA)") (class "Default")
      (node (ref "LED14") (pin "A") (pinfunction "A_A") (pintype "passive"))
      (node (ref "R56") (pin "1") (pinfunction "1_1") (pintype "passive"))
    )
    (net (code "79") (name "Net-(RJ1-LED_G-)") (class "Default")
      (node (ref "R34") (pin "1") (pinfunction "1_1") (pintype "passive"))
      (node (ref "RJ1") (pin "10") (pinfunction "LED_G-_10") (pintype "passive"))
    )
    (net (code "80") (name "Net-(RJ1-LED_Y-)") (class "Default")
      (node (ref "R33") (pin "1") (pinfunction "1_1") (pintype "passive"))
      (node (ref "RJ1") (pin "11") (pinfunction "LED_Y-_11") (pintype "passive"))
    )
    (net (code "81") (name "Net-(U4-MDIX_EN)") (class "Default")
      (node (ref "R14") (pin "1") (pinfunction "1_1") (pintype "passive"))
      (node (ref "U4") (pin "41") (pinfunction "MDIX_EN_41") (pintype "bidirectional"))
    )
    (net (code "82") (name "Net-(U4-NRESET)") (class "Default")
      (node (ref "R36") (pin "2") (pinfunction "2_2") (pintype "passive"))
      (node (ref "U4") (pin "12") (pinfunction "NRESET_12") (pintype "bidirectional"))
    )
    (net (code "83") (name "Net-(U4-USBRBIAS)") (class "Default")
      (node (ref "R35") (pin "2") (pinfunction "2_2") (pintype "passive"))
      (node (ref "U4") (pin "63") (pinfunction "USBRBIAS_63") (pintype "bidirectional"))
    )
    (net (code "84") (name "Net-(U4-VBUS_DET)") (class "Default")
      (node (ref "R12") (pin "1") (pinfunction "1_1") (pintype "passive"))
      (node (ref "U4") (pin "11") (pinfunction "VBUS_DET_11") (pintype "bidirectional"))
    )
    (net (code "85") (name "Net-(U10-3V3OUT)") (class "Default")
      (node (ref "C77") (pin "2") (pinfunction "2_2") (pintype "passive"))
      (node (ref "U10") (pin "13") (pinfunction "3V3OUT_13") (pintype "bidirectional"))
    )
    (net (code "86") (name "Net-(U17-Y)") (class "Default")
      (node (ref "U17") (pin "4") (pinfunction "Y_4") (pintype "bidirectional"))
      (node (ref "U18") (pin "1") (pinfunction "ENA_1") (pintype "bidirectional"))
    )
    (net (code "87") (name "Net-(U18-ENB)") (class "Default")
      (node (ref "U18") (pin "4") (pinfunction "ENB_4") (pintype "bidirectional"))
      (node (ref "U20") (pin "4") (pinfunction "Y_4") (pintype "bidirectional"))
    )
    (net (code "88") (name "PRTCTL2") (class "Default")
      (node (ref "U17") (pin "2") (pinfunction "B_2") (pintype "bidirectional"))
      (node (ref "U18") (pin "2") (pinfunction "FLGA_2") (pintype "bidirectional"))
      (node (ref "U4") (pin "14") (pinfunction "PRTCTL2_14") (pintype "bidirectional"))
    )
    (net (code "89") (name "PRTCTL3") (class "Default")
      (node (ref "U18") (pin "3") (pinfunction "FLGB_3") (pintype "bidirectional"))
      (node (ref "U20") (pin "2") (pinfunction "B_2") (pintype "bidirectional"))
      (node (ref "U4") (pin "16") (pinfunction "PRTCTL3_16") (pintype "bidirectional"))
    )
    (net (code "90") (name "PRTCTL4") (class "Default")
      (node (ref "U19") (pin "1") (pinfunction "ENA_1") (pintype "bidirectional"))
      (node (ref "U19") (pin "2") (pinfunction "FLGA_2") (pintype "bidirectional"))
      (node (ref "U4") (pin "17") (pinfunction "PRTCTL4_17") (pintype "bidirectional"))
    )
    (net (code "91") (name "PRTCTL5") (class "Default")
      (node (ref "U19") (pin "3") (pinfunction "FLGB_3") (pintype "bidirectional"))
      (node (ref "U19") (pin "4") (pinfunction "ENB_4") (pintype "bidirectional"))
      (node (ref "U4") (pin "18") (pinfunction "PRTCTL5_18") (pintype "bidirectional"))
    )
    (net (code "92") (name "PWR1") (class "Default")
      (node (ref "J16") (pin "6") (pinfunction "6_6") (pintype "passive"))
      (node (ref "R56") (pin "2") (pinfunction "2_2") (pintype "passive"))
      (node (ref "U18") (pin "8") (pinfunction "OUTA_8") (pintype "bidirectional"))
    )
    (net (code "93") (name "PWR2") (class "Default")
      (node (ref "J17") (pin "6") (pinfunction "6_6") (pintype "passive"))
      (node (ref "R55") (pin "2") (pinfunction "2_2") (pintype "passive"))
      (node (ref "U18") (pin "5") (pinfunction "OUTB_5") (pintype "bidirectional"))
    )
    (net (code "94") (name "PWR3") (class "Default")
      (node (ref "J3") (pin "1") (pinfunction "VCC_1") (pintype "bidirectional"))
      (node (ref "R52") (pin "2") (pinfunction "2_2") (pintype "passive"))
      (node (ref "U19") (pin "8") (pinfunction "OUTA_8") (pintype "bidirectional"))
    )
    (net (code "95") (name "PWR4") (class "Default")
      (node (ref "R37") (pin "2") (pinfunction "2_2") (pintype "passive"))
      (node (ref "U19") (pin "5") (pinfunction "OUTB_5") (pintype "bidirectional"))
    )
    (net (code "96") (name "RD_N") (class "Default")
      (node (ref "C32") (pin "2") (pinfunction "2_2") (pintype "passive"))
      (node (ref "R32") (pin "1") (pinfunction "1_1") (pintype "passive"))
      (node (ref "RJ1") (pin "6") (pinfunction "RD-_6") (pintype "passive"))
      (node (ref "U4") (pin "53") (pinfunction "RXN_53") (pintype "bidirectional"))
    )
    (net (code "97") (name "RD_P") (class "Default")
      (node (ref "C31") (pin "2") (pinfunction "2_2") (pintype "passive"))
      (node (ref "R31") (pin "1") (pinfunction "1_1") (pintype "passive"))
      (node (ref "RJ1") (pin "3") (pinfunction "RD+_3") (pintype "passive"))
      (node (ref "U4") (pin "52") (pinfunction "RXP_52") (pintype "bidirectional"))
    )
    (net (code "98") (name "RESET") (class "Default")
      (node (ref "U10") (pin "14") (pinfunction "~{RESET}_14") (pintype "bidirectional"))
    )
    (net (code "99") (name "RO2") (class "Default")
      (node (ref "U15") (pin "3") (pinfunction "3_3") (pintype "bidirectional"))
      (node (ref "U9") (pin "1") (pinfunction "1_1") (pintype "bidirectional"))
    )
    (net (code "100") (name "RO2O") (class "Default")
      (node (ref "J20") (pin "61") (pinfunction "GP130_61") (pintype "bidirectional"))
      (node (ref "U15") (pin "4") (pinfunction "4_4") (pintype "bidirectional"))
    )
    (net (code "101") (name "RTS") (class "Default")
      (node (ref "J20") (pin "63") (pinfunction "GP129_63") (pintype "bidirectional"))
      (node (ref "U14") (pin "3") (pinfunction "3_3") (pintype "bidirectional"))
    )
    (net (code "102") (name "RTSO") (class "Default")
      (node (ref "U14") (pin "4") (pinfunction "4_4") (pintype "bidirectional"))
      (node (ref "U9") (pin "2") (pinfunction "2_2") (pintype "bidirectional"))
      (node (ref "U9") (pin "3") (pinfunction "3_3") (pintype "bidirectional"))
    )
    (net (code "103") (name "SCED_N") (class "Default")
      (node (ref "J20") (pin "22") (pinfunction "GP134_22") (pintype "bidirectional"))
      (node (ref "U11") (pin "4") (pinfunction "4_4") (pintype "bidirectional"))
    )
    (net (code "104") (name "SCED_P") (class "Default")
      (node (ref "J20") (pin "27") (pinfunction "GP135_27") (pintype "bidirectional"))
      (node (ref "U12") (pin "3") (pinfunction "3_3") (pintype "bidirectional"))
    )
    (net (code "105") (name "SCON_N") (class "Default")
      (node (ref "J7") (pin "3") (pinfunction "3_3") (pintype "passive"))
      (node (ref "U10") (pin "12") (pinfunction "USBDM_12") (pintype "bidirectional"))
    )
    (net (code "106") (name "SCON_P") (class "Default")
      (node (ref "J7") (pin "2") (pinfunction "2_2") (pintype "passive"))
      (node (ref "U10") (pin "11") (pinfunction "USBDP_11") (pintype "bidirectional"))
    )
    (net (code "107") (name "SC_N") (class "Default")
      (node (ref "U10") (pin "4") (pinfunction "RXD_4") (pintype "bidirectional"))
      (node (ref "U11") (pin "3") (pinfunction "3_3") (pintype "bidirectional"))
    )
    (net (code "108") (name "SC_P") (class "Default")
      (node (ref "U10") (pin "20") (pinfunction "TXD_20") (pintype "bidirectional"))
      (node (ref "U12") (pin "4") (pinfunction "4_4") (pintype "bidirectional"))
    )
    (net (code "109") (name "TD_N") (class "Default")
      (node (ref "C30") (pin "2") (pinfunction "2_2") (pintype "passive"))
      (node (ref "R30") (pin "1") (pinfunction "1_1") (pintype "passive"))
      (node (ref "RJ1") (pin "2") (pinfunction "TD-_2") (pintype "passive"))
      (node (ref "U4") (pin "56") (pinfunction "TXN_56") (pintype "bidirectional"))
    )
    (net (code "110") (name "TD_P") (class "Default")
      (node (ref "C26") (pin "2") (pinfunction "2_2") (pintype "passive"))
      (node (ref "R22") (pin "1") (pinfunction "1_1") (pintype "passive"))
      (node (ref "RJ1") (pin "1") (pinfunction "TD+_1") (pintype "passive"))
      (node (ref "U4") (pin "55") (pinfunction "TXP_55") (pintype "bidirectional"))
    )
    (net (code "111") (name "ULCEN") (class "Default")
      (node (ref "J20") (pin "42") (pinfunction "GP15_42") (pintype "bidirectional"))
      (node (ref "U21") (pin "3") (pinfunction "3_3") (pintype "bidirectional"))
    )
    (net (code "112") (name "ULCENO") (class "Default")
      (node (ref "U20") (pin "1") (pinfunction "A_1") (pintype "bidirectional"))
      (node (ref "U21") (pin "4") (pinfunction "4_4") (pintype "bidirectional"))
    )
    (net (code "113") (name "ULC_N") (class "Default")
      (node (ref "J17") (pin "8") (pinfunction "8_8") (pintype "passive"))
      (node (ref "U4") (pin "1") (pinfunction "USBDM2_1") (pintype "bidirectional"))
    )
    (net (code "114") (name "ULC_P") (class "Default")
      (node (ref "J17") (pin "7") (pinfunction "7_7") (pintype "passive"))
      (node (ref "U4") (pin "2") (pinfunction "USBDP2_2") (pintype "bidirectional"))
    )
    (net (code "115") (name "USB0_N") (class "Default")
      (node (ref "J20") (pin "18") (pinfunction "USB_DN_18") (pintype "bidirectional"))
      (node (ref "U4") (pin "58") (pinfunction "USBDM0_58") (pintype "bidirectional"))
    )
    (net (code "116") (name "USB0_P") (class "Default")
      (node (ref "J20") (pin "16") (pinfunction "USB_DP_16") (pintype "bidirectional"))
      (node (ref "U4") (pin "59") (pinfunction "USBDP0_59") (pintype "bidirectional"))
    )
    (net (code "117") (name "USBA_N") (class "Default")
      (node (ref "J3") (pin "2") (pinfunction "D-_2") (pintype "bidirectional"))
      (node (ref "U4") (pin "6") (pinfunction "USBDM4_6") (pintype "bidirectional"))
    )
    (net (code "118") (name "USBA_P") (class "Default")
      (node (ref "J3") (pin "3") (pinfunction "D+_3") (pintype "bidirectional"))
      (node (ref "U4") (pin "7") (pinfunction "USBDP4_7") (pintype "bidirectional"))
    )
    (net (code "119") (name "USBMCU_N") (class "Default")
      (node (ref "J6") (pin "8") (pinfunction "8_8") (pintype "passive"))
      (node (ref "U4") (pin "8") (pinfunction "USBDM5_8") (pintype "bidirectional"))
    )
    (net (code "120") (name "USBMCU_P") (class "Default")
      (node (ref "J6") (pin "7") (pinfunction "7_7") (pintype "passive"))
      (node (ref "U4") (pin "9") (pinfunction "USBDP5_9") (pintype "bidirectional"))
    )
    (net (code "121") (name "VDD18C") (class "Default")
      (node (ref "C83") (pin "2") (pinfunction "2_2") (pintype "passive"))
      (node (ref "C84") (pin "2") (pinfunction "2_2") (pintype "passive"))
      (node (ref "C85") (pin "2") (pinfunction "2_2") (pintype "passive"))
      (node (ref "U4") (pin "15") (pinfunction "V18COR_15") (pintype "bidirectional"))
      (node (ref "U4") (pin "38") (pinfunction "V18COR_38") (pintype "bidirectional"))
    )
    (net (code "122") (name "VDD18ETH") (class "Default")
      (node (ref "C74") (pin "2") (pinfunction "2_2") (pintype "passive"))
      (node (ref "FB4") (pin "2") (pinfunction "2_2") (pintype "passive"))
      (node (ref "U4") (pin "48") (pinfunction "VDD18ETHPLL_48") (pintype "bidirectional"))
    )
    (net (code "123") (name "VDD18USB") (class "Default")
      (node (ref "C73") (pin "2") (pinfunction "2_2") (pintype "passive"))
      (node (ref "FB4") (pin "1") (pinfunction "1_1") (pintype "passive"))
      (node (ref "U4") (pin "62") (pinfunction "VDD18USBPLL_62") (pintype "bidirectional"))
    )
    (net (code "124") (name "VDD33A") (class "Default")
      (node (ref "C13") (pin "2") (pinfunction "2_2") (pintype "passive"))
      (node (ref "C14") (pin "2") (pinfunction "2_2") (pintype "passive"))
      (node (ref "C18") (pin "2") (pinfunction "2_2") (pintype "passive"))
      (node (ref "C19") (pin "2") (pinfunction "2_2") (pintype "passive"))
      (node (ref "C20") (pin "2") (pinfunction "2_2") (pintype "passive"))
      (node (ref "C21") (pin "2") (pinfunction "2_2") (pintype "passive"))
      (node (ref "C22") (pin "2") (pinfunction "2_2") (pintype "passive"))
      (node (ref "FB1") (pin "1") (pinfunction "1_1") (pintype "passive"))
      (node (ref "U4") (pin "10") (pinfunction "VDD33A_10") (pintype "bidirectional"))
      (node (ref "U4") (pin "49") (pinfunction "VDD33A_49") (pintype "bidirectional"))
      (node (ref "U4") (pin "5") (pinfunction "VDD33A_5") (pintype "bidirectional"))
      (node (ref "U4") (pin "51") (pinfunction "VDD33A_51") (pintype "bidirectional"))
      (node (ref "U4") (pin "54") (pinfunction "VDD33A_54") (pintype "bidirectional"))
      (node (ref "U4") (pin "57") (pinfunction "VDD33A_57") (pintype "bidirectional"))
      (node (ref "U4") (pin "64") (pinfunction "VDD33A_64") (pintype "bidirectional"))
    )
    (net (code "125") (name "XI") (class "Default")
      (node (ref "C12") (pin "2") (pinfunction "2_2") (pintype "passive"))
      (node (ref "Q2") (pin "2") (pinfunction "2_2") (pintype "passive"))
      (node (ref "R11") (pin "2") (pinfunction "2_2") (pintype "passive"))
      (node (ref "U4") (pin "61") (pinfunction "XI_61") (pintype "bidirectional"))
    )
    (net (code "126") (name "XO") (class "Default")
      (node (ref "C11") (pin "2") (pinfunction "2_2") (pintype "passive"))
      (node (ref "Q2") (pin "1") (pinfunction "1_1") (pintype "passive"))
      (node (ref "R11") (pin "1") (pinfunction "1_1") (pintype "passive"))
      (node (ref "U4") (pin "60") (pinfunction "XO_60") (pintype "bidirectional"))
    )
    (net (code "127") (name "unconnected-(J20-3.3V-Pad8)") (class "Default")
      (node (ref "J20") (pin "8") (pinfunction "3.3V_8") (pintype "bidirectional"))
    )
    (net (code "128") (name "unconnected-(J20-3.3V-Pad10)") (class "Default")
      (node (ref "J20") (pin "10") (pinfunction "3.3V_10") (pintype "bidirectional"))
    )
    (net (code "129") (name "unconnected-(J20-FAULT-Pad19)") (class "Default")
      (node (ref "J20") (pin "19") (pinfunction "FAULT_19") (pintype "bidirectional"))
    )
    (net (code "130") (name "unconnected-(J20-FW_RX-Pad69)") (class "Default")
      (node (ref "J20") (pin "69") (pinfunction "FW_RX_69") (pintype "bidirectional"))
    )
    (net (code "131") (name "unconnected-(J20-GP12-Pad35)") (class "Default")
      (node (ref "J20") (pin "35") (pinfunction "GP12_35") (pintype "bidirectional"))
    )
    (net (code "132") (name "unconnected-(J20-GP13-Pad33)") (class "Default")
      (node (ref "J20") (pin "33") (pinfunction "GP13_33") (pintype "bidirectional"))
    )
    (net (code "133") (name "unconnected-(J20-GP19-Pad41)") (class "Default")
      (node (ref "J20") (pin "41") (pinfunction "GP19_41") (pintype "bidirectional"))
    )
    (net (code "134") (name "unconnected-(J20-GP20-Pad43)") (class "Default")
      (node (ref "J20") (pin "43") (pinfunction "GP20_43") (pintype "bidirectional"))
    )
    (net (code "135") (name "unconnected-(J20-GP27-Pad45)") (class "Default")
      (node (ref "J20") (pin "45") (pinfunction "GP27_45") (pintype "bidirectional"))
    )
    (net (code "136") (name "unconnected-(J20-GP28-Pad47)") (class "Default")
      (node (ref "J20") (pin "47") (pinfunction "GP28_47") (pintype "bidirectional"))
    )
    (net (code "137") (name "unconnected-(J20-GP77-Pad60)") (class "Default")
      (node (ref "J20") (pin "60") (pinfunction "GP77_60") (pintype "bidirectional"))
    )
    (net (code "138") (name "unconnected-(J20-GP78-Pad58)") (class "Default")
      (node (ref "J20") (pin "58") (pinfunction "GP78_58") (pintype "bidirectional"))
    )
    (net (code "139") (name "unconnected-(J20-GP79-Pad62)") (class "Default")
      (node (ref "J20") (pin "62") (pinfunction "GP79_62") (pintype "bidirectional"))
    )
    (net (code "140") (name "unconnected-(J20-GP80-Pad66)") (class "Default")
      (node (ref "J20") (pin "66") (pinfunction "GP80_66") (pintype "bidirectional"))
    )
    (net (code "141") (name "unconnected-(J20-GP81-Pad70)") (class "Default")
      (node (ref "J20") (pin "70") (pinfunction "GP81_70") (pintype "bidirectional"))
    )
    (net (code "142") (name "unconnected-(J20-GP82-Pad64)") (class "Default")
      (node (ref "J20") (pin "64") (pinfunction "GP82_64") (pintype "bidirectional"))
    )
    (net (code "143") (name "unconnected-(J20-GP83-Pad68)") (class "Default")
      (node (ref "J20") (pin "68") (pinfunction "GP83_68") (pintype "bidirectional"))
    )
    (net (code "144") (name "unconnected-(J20-GP84-Pad44)") (class "Default")
      (node (ref "J20") (pin "44") (pinfunction "GP84_44") (pintype "bidirectional"))
    )
    (net (code "145") (name "unconnected-(J20-GP109-Pad55)") (class "Default")
      (node (ref "J20") (pin "55") (pinfunction "GP109_55") (pintype "bidirectional"))
    )
    (net (code "146") (name "unconnected-(J20-GP110-Pad53)") (class "Default")
      (node (ref "J20") (pin "53") (pinfunction "GP110_53") (pintype "bidirectional"))
    )
    (net (code "147") (name "unconnected-(J20-GP111-Pad51)") (class "Default")
      (node (ref "J20") (pin "51") (pinfunction "GP111_51") (pintype "bidirectional"))
    )
    (net (code "148") (name "unconnected-(J20-GP114-Pad59)") (class "Default")
      (node (ref "J20") (pin "59") (pinfunction "GP114_59") (pintype "bidirectional"))
    )
    (net (code "149") (name "unconnected-(J20-GP115-Pad57)") (class "Default")
      (node (ref "J20") (pin "57") (pinfunction "GP115_57") (pintype "bidirectional"))
    )
    (net (code "150") (name "unconnected-(J20-GP128-Pad65)") (class "Default")
      (node (ref "J20") (pin "65") (pinfunction "GP128_65") (pintype "bidirectional"))
    )
    (net (code "151") (name "unconnected-(J20-MSIC_SLP_CLK3-Pad7)") (class "Default")
      (node (ref "J20") (pin "7") (pinfunction "MSIC_SLP_CLK3_7") (pintype "bidirectional"))
    )
    (net (code "152") (name "unconnected-(J20-NC-Pad29)") (class "Default")
      (node (ref "J20") (pin "29") (pinfunction "NC_29") (pintype "bidirectional"))
    )
    (net (code "153") (name "unconnected-(J20-NC-Pad38)") (class "Default")
      (node (ref "J20") (pin "38") (pinfunction "NC_38") (pintype "bidirectional"))
    )
    (net (code "154") (name "unconnected-(J20-NC-Pad40)") (class "Default")
      (node (ref "J20") (pin "40") (pinfunction "NC_40") (pintype "bidirectional"))
    )
    (net (code "155") (name "unconnected-(J20-NC-Pad49)") (class "Default")
      (node (ref "J20") (pin "49") (pinfunction "NC_49") (pintype "bidirectional"))
    )
    (net (code "156") (name "unconnected-(J20-OSCCLKOUT-Pad67)") (class "Default")
      (node (ref "J20") (pin "67") (pinfunction "OSCCLKOUT_67") (pintype "bidirectional"))
    )
    (net (code "157") (name "unconnected-(J20-PSW-Pad21)") (class "Default")
      (node (ref "J20") (pin "21") (pinfunction "PSW_21") (pintype "bidirectional"))
    )
    (net (code "158") (name "unconnected-(J20-RSTOUT-Pad36)") (class "Default")
      (node (ref "J20") (pin "36") (pinfunction "RSTOUT_36") (pintype "bidirectional"))
    )
    (net (code "159") (name "unconnected-(J20-RX_MODE-Pad31)") (class "Default")
      (node (ref "J20") (pin "31") (pinfunction "RX_MODE_31") (pintype "bidirectional"))
    )
    (net (code "160") (name "unconnected-(J20-USB_ID-Pad3)") (class "Default")
      (node (ref "J20") (pin "3") (pinfunction "USB_ID_3") (pintype "bidirectional"))
    )
    (net (code "161") (name "unconnected-(J20-USB_VBUS-Pad20)") (class "Default")
      (node (ref "J20") (pin "20") (pinfunction "USB_VBUS_20") (pintype "bidirectional"))
    )
    (net (code "162") (name "unconnected-(J20-VBAT_BKUP-Pad23)") (class "Default")
      (node (ref "J20") (pin "23") (pinfunction "VBAT_BKUP_23") (pintype "bidirectional"))
    )
    (net (code "163") (name "unconnected-(RJ1-NC-Pad7)") (class "Default")
      (node (ref "RJ1") (pin "7") (pinfunction "NC_7") (pintype "passive"))
    )
    (net (code "164") (name "unconnected-(U4-CLK24_OUT-Pad45)") (class "Default")
      (node (ref "U4") (pin "45") (pinfunction "CLK24_OUT_45") (pintype "bidirectional"))
    )
    (net (code "165") (name "unconnected-(U4-GPIO3-Pad35)") (class "Default")
      (node (ref "U4") (pin "35") (pinfunction "GPIO3_35") (pintype "bidirectional"))
    )
    (net (code "166") (name "unconnected-(U4-GPIO4-Pad36)") (class "Default")
      (node (ref "U4") (pin "36") (pinfunction "GPIO4_36") (pintype "bidirectional"))
    )
    (net (code "167") (name "unconnected-(U4-GPIO5-Pad37)") (class "Default")
      (node (ref "U4") (pin "37") (pinfunction "GPIO5_37") (pintype "bidirectional"))
    )
    (net (code "168") (name "unconnected-(U4-GPIO6-Pad42)") (class "Default")
      (node (ref "U4") (pin "42") (pinfunction "GPIO6_42") (pintype "bidirectional"))
    )
    (net (code "169") (name "unconnected-(U4-GPIO7-Pad43)") (class "Default")
      (node (ref "U4") (pin "43") (pinfunction "GPIO7_43") (pintype "bidirectional"))
    )
    (net (code "170") (name "unconnected-(U4-NTRST-Pad28)") (class "Default")
      (node (ref "U4") (pin "28") (pinfunction "NTRST_28") (pintype "bidirectional"))
    )
    (net (code "171") (name "unconnected-(U4-TCK-Pad32)") (class "Default")
      (node (ref "U4") (pin "32") (pinfunction "TCK_32") (pintype "bidirectional"))
    )
    (net (code "172") (name "unconnected-(U4-TDI-Pad30)") (class "Default")
      (node (ref "U4") (pin "30") (pinfunction "TDI_30") (pintype "bidirectional"))
    )
    (net (code "173") (name "unconnected-(U4-TDO-Pad31)") (class "Default")
      (node (ref "U4") (pin "31") (pinfunction "TDO_31") (pintype "bidirectional"))
    )
    (net (code "174") (name "unconnected-(U4-TEST1-Pad13)") (class "Default")
      (node (ref "U4") (pin "13") (pinfunction "TEST1_13") (pintype "bidirectional"))
    )
    (net (code "175") (name "unconnected-(U4-TEST4-Pad47)") (class "Default")
      (node (ref "U4") (pin "47") (pinfunction "TEST4_47") (pintype "bidirectional"))
    )
    (net (code "176") (name "unconnected-(U4-TMS-Pad29)") (class "Default")
      (node (ref "U4") (pin "29") (pinfunction "TMS_29") (pintype "bidirectional"))
    )
    (net (code "177") (name "unconnected-(U10-CBUS0-Pad18)") (class "Default")
      (node (ref "U10") (pin "18") (pinfunction "CBUS0_18") (pintype "bidirectional"))
    )
    (net (code "178") (name "unconnected-(U10-CBUS3-Pad19)") (class "Default")
      (node (ref "U10") (pin "19") (pinfunction "CBUS3_19") (pintype "bidirectional"))
    )
    (net (code "179") (name "unconnected-(U10-~{CTS}-Pad9)") (class "Default")
      (node (ref "U10") (pin "9") (pinfunction "~{CTS}_9") (pintype "bidirectional"))
    )
    (net (code "180") (name "unconnected-(U10-~{DCD}-Pad8)") (class "Default")
      (node (ref "U10") (pin "8") (pinfunction "~{DCD}_8") (pintype "bidirectional"))
    )
    (net (code "181") (name "unconnected-(U10-~{DSR}-Pad7)") (class "Default")
      (node (ref "U10") (pin "7") (pinfunction "~{DSR}_7") (pintype "bidirectional"))
    )
    (net (code "182") (name "unconnected-(U10-~{RI}-Pad5)") (class "Default")
      (node (ref "U10") (pin "5") (pinfunction "~{RI}_5") (pintype "bidirectional"))
    )
    (net (code "183") (name "unconnected-(U10-~{RTS}-Pad2)") (class "Default")
      (node (ref "U10") (pin "2") (pinfunction "~{RTS}_2") (pintype "bidirectional"))
    )
    (net (code "184") (name "unconnected-(VR1-OUT-Pad2)") (class "Default")
      (node (ref "VR1") (pin "2") (pinfunction "OUT_2") (pintype "bidirectional"))
    )
    (net (code "185") (name "~{DTR}") (class "Default")
      (node (ref "U10") (pin "1") (pinfunction "~{DTR}_1") (pintype "bidirectional"))
    )
    (net (code "186") (name "~{ENBL_MOD}") (class "Default")
      (node (ref "J16") (pin "2") (pinfunction "2_2") (pintype "passive"))
      (node (ref "J17") (pin "2") (pinfunction "2_2") (pintype "passive"))
      (node (ref "J18") (pin "2") (pinfunction "2_2") (pintype "bidirectional"))
      (node (ref "J6") (pin "2") (pinfunction "2_2") (pintype "passive"))
    )
    (net (code "187") (name "~{PWRBTN}") (class "Default")
      (node (ref "J1") (pin "1") (pinfunction "1_1") (pintype "passive"))
      (node (ref "J20") (pin "17") (pinfunction "PWRBTN#_17") (pintype "bidirectional"))
      (node (ref "R48") (pin "1") (pinfunction "1_1") (pintype "passive"))
    )
    (net (code "188") (name "~{RESET}") (class "Default")
      (node (ref "R36") (pin "1") (pinfunction "1_1") (pintype "passive"))
    )
    (net (code "189") (name "~{RXLED}") (class "Default")
      (node (ref "LED9") (pin "C") (pinfunction "C_C") (pintype "passive"))
      (node (ref "U10") (pin "10") (pinfunction "CBUS2_10") (pintype "bidirectional"))
    )
    (net (code "190") (name "~{TXLED}") (class "Default")
      (node (ref "LED8") (pin "C") (pinfunction "C_C") (pintype "passive"))
      (node (ref "U10") (pin "17") (pinfunction "CBUS1_17") (pintype "bidirectional"))
    )
  )
)
